# LcsNodes-Extension-Turnout-Servo-and-Rel.net
KiCad netlist of a schematic drawn in EasyEDA
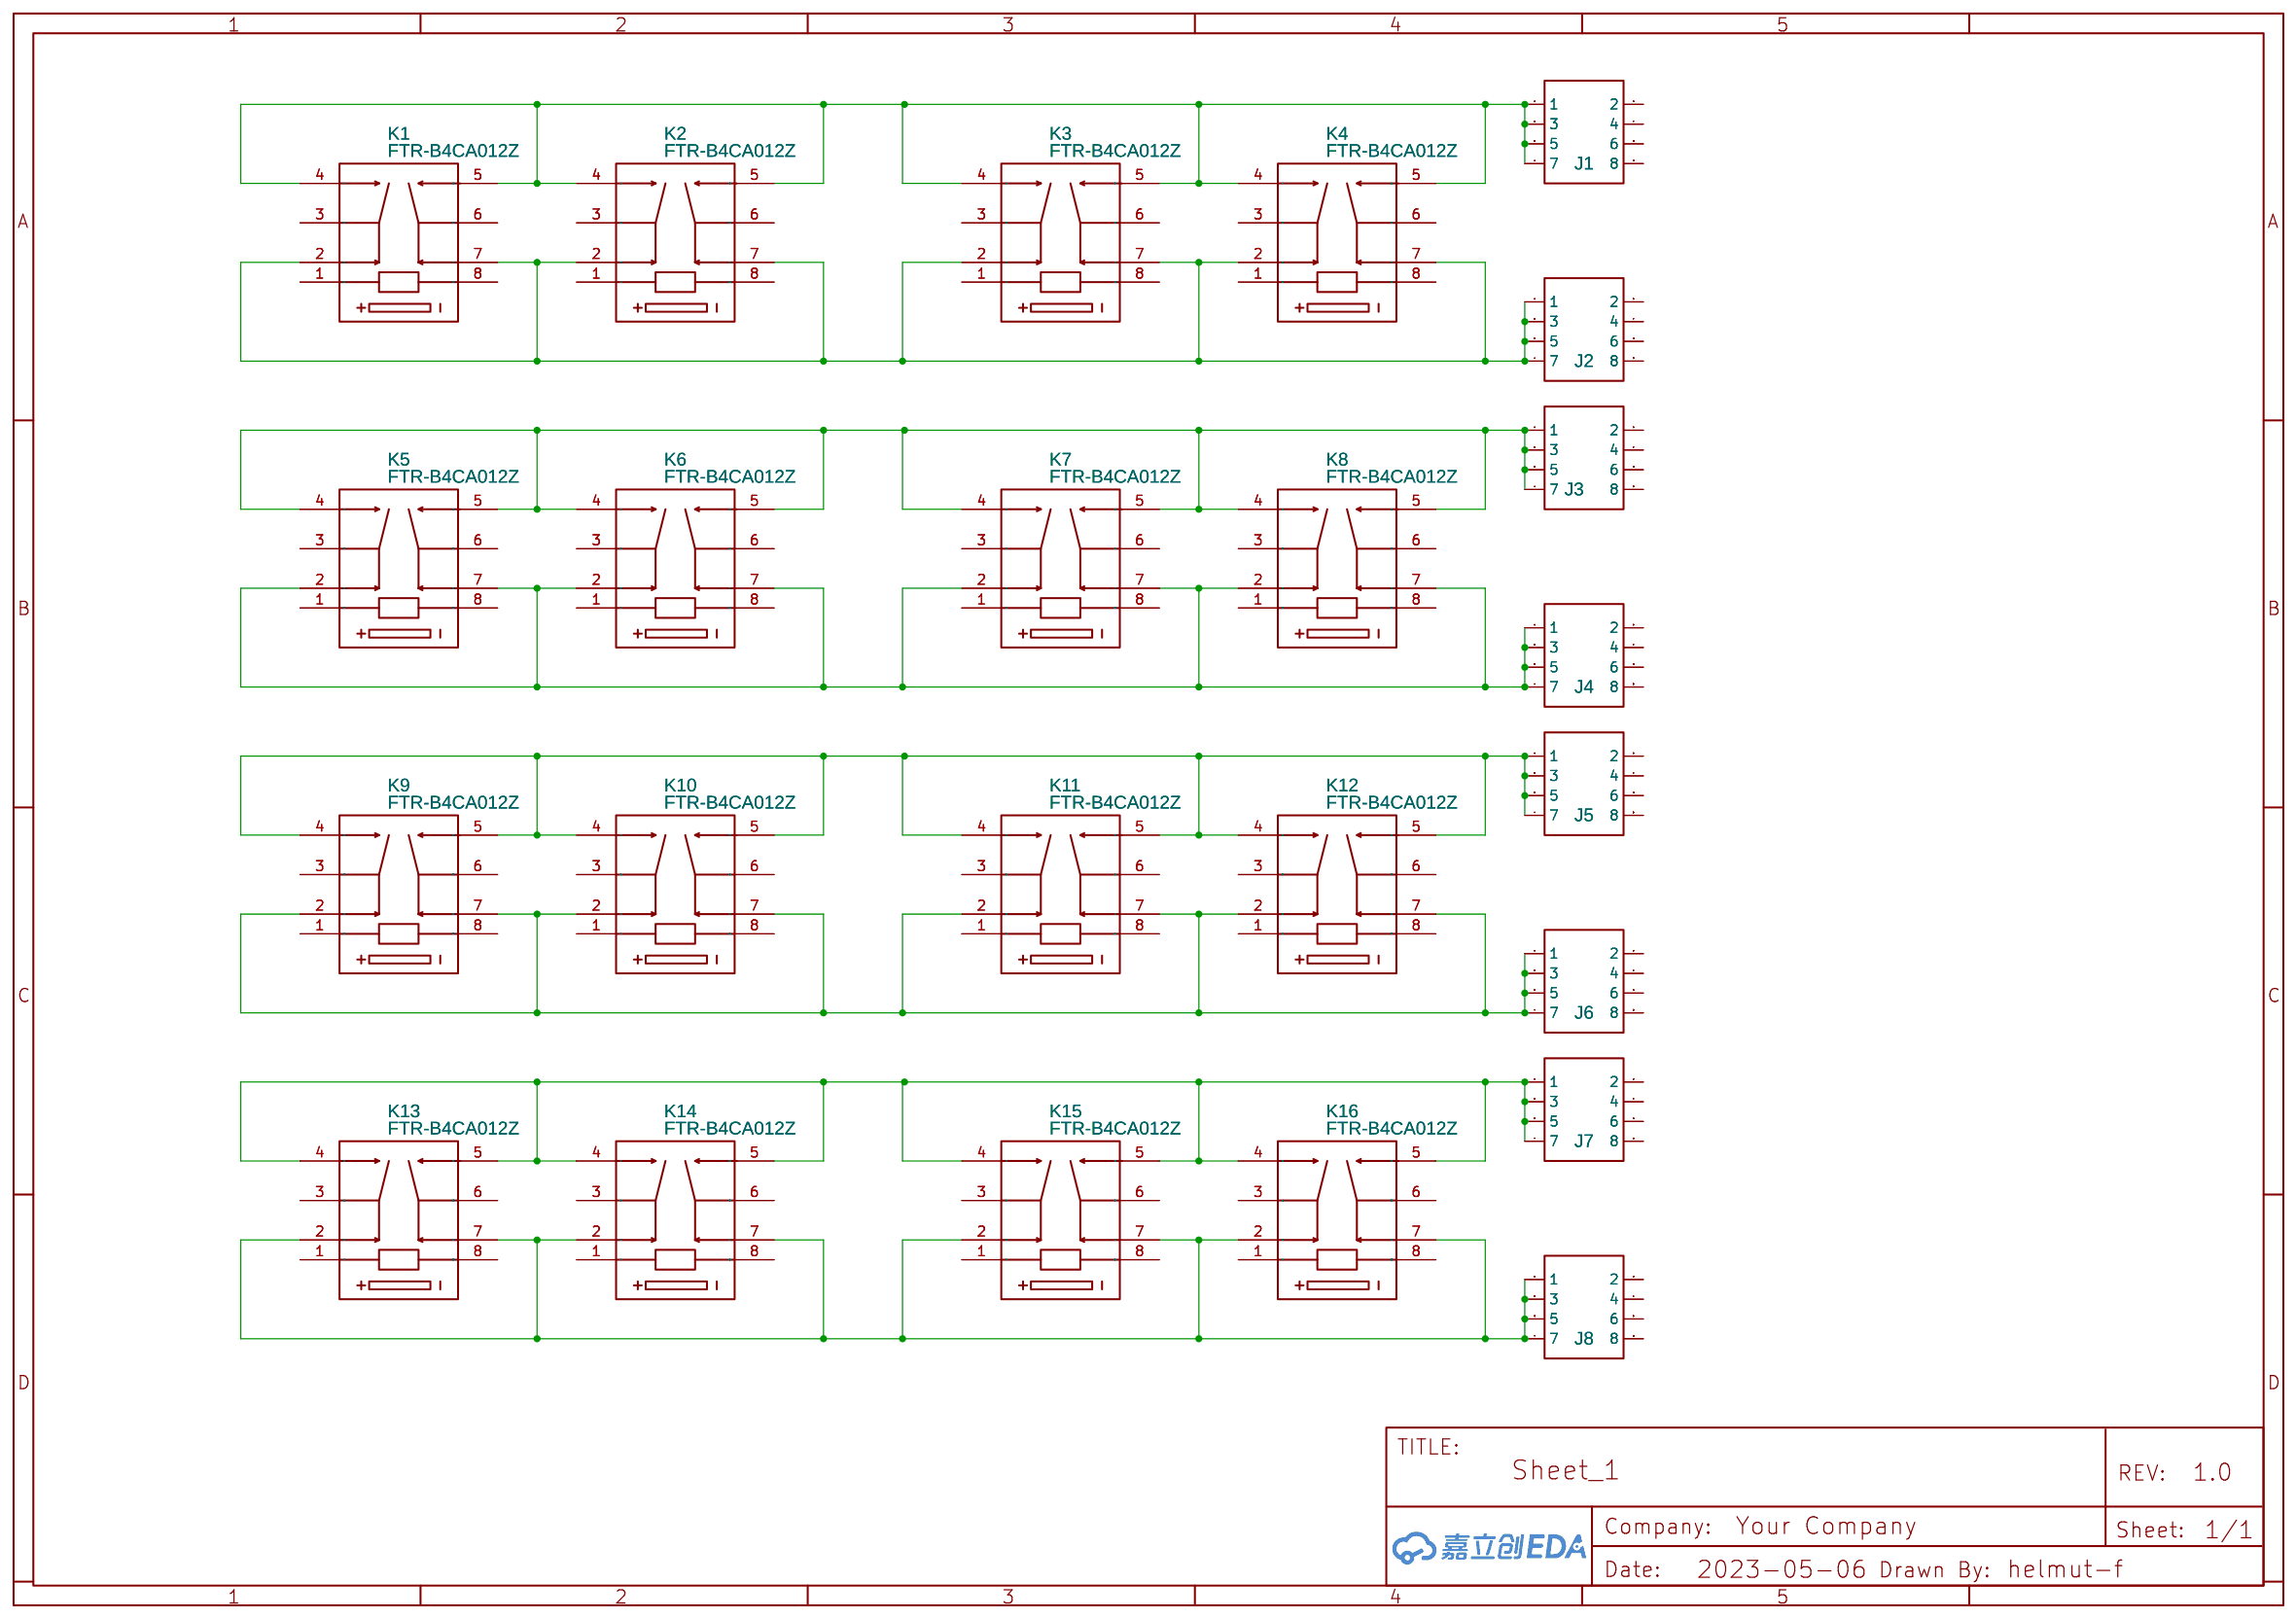
[diagram p0: Sheet_1]
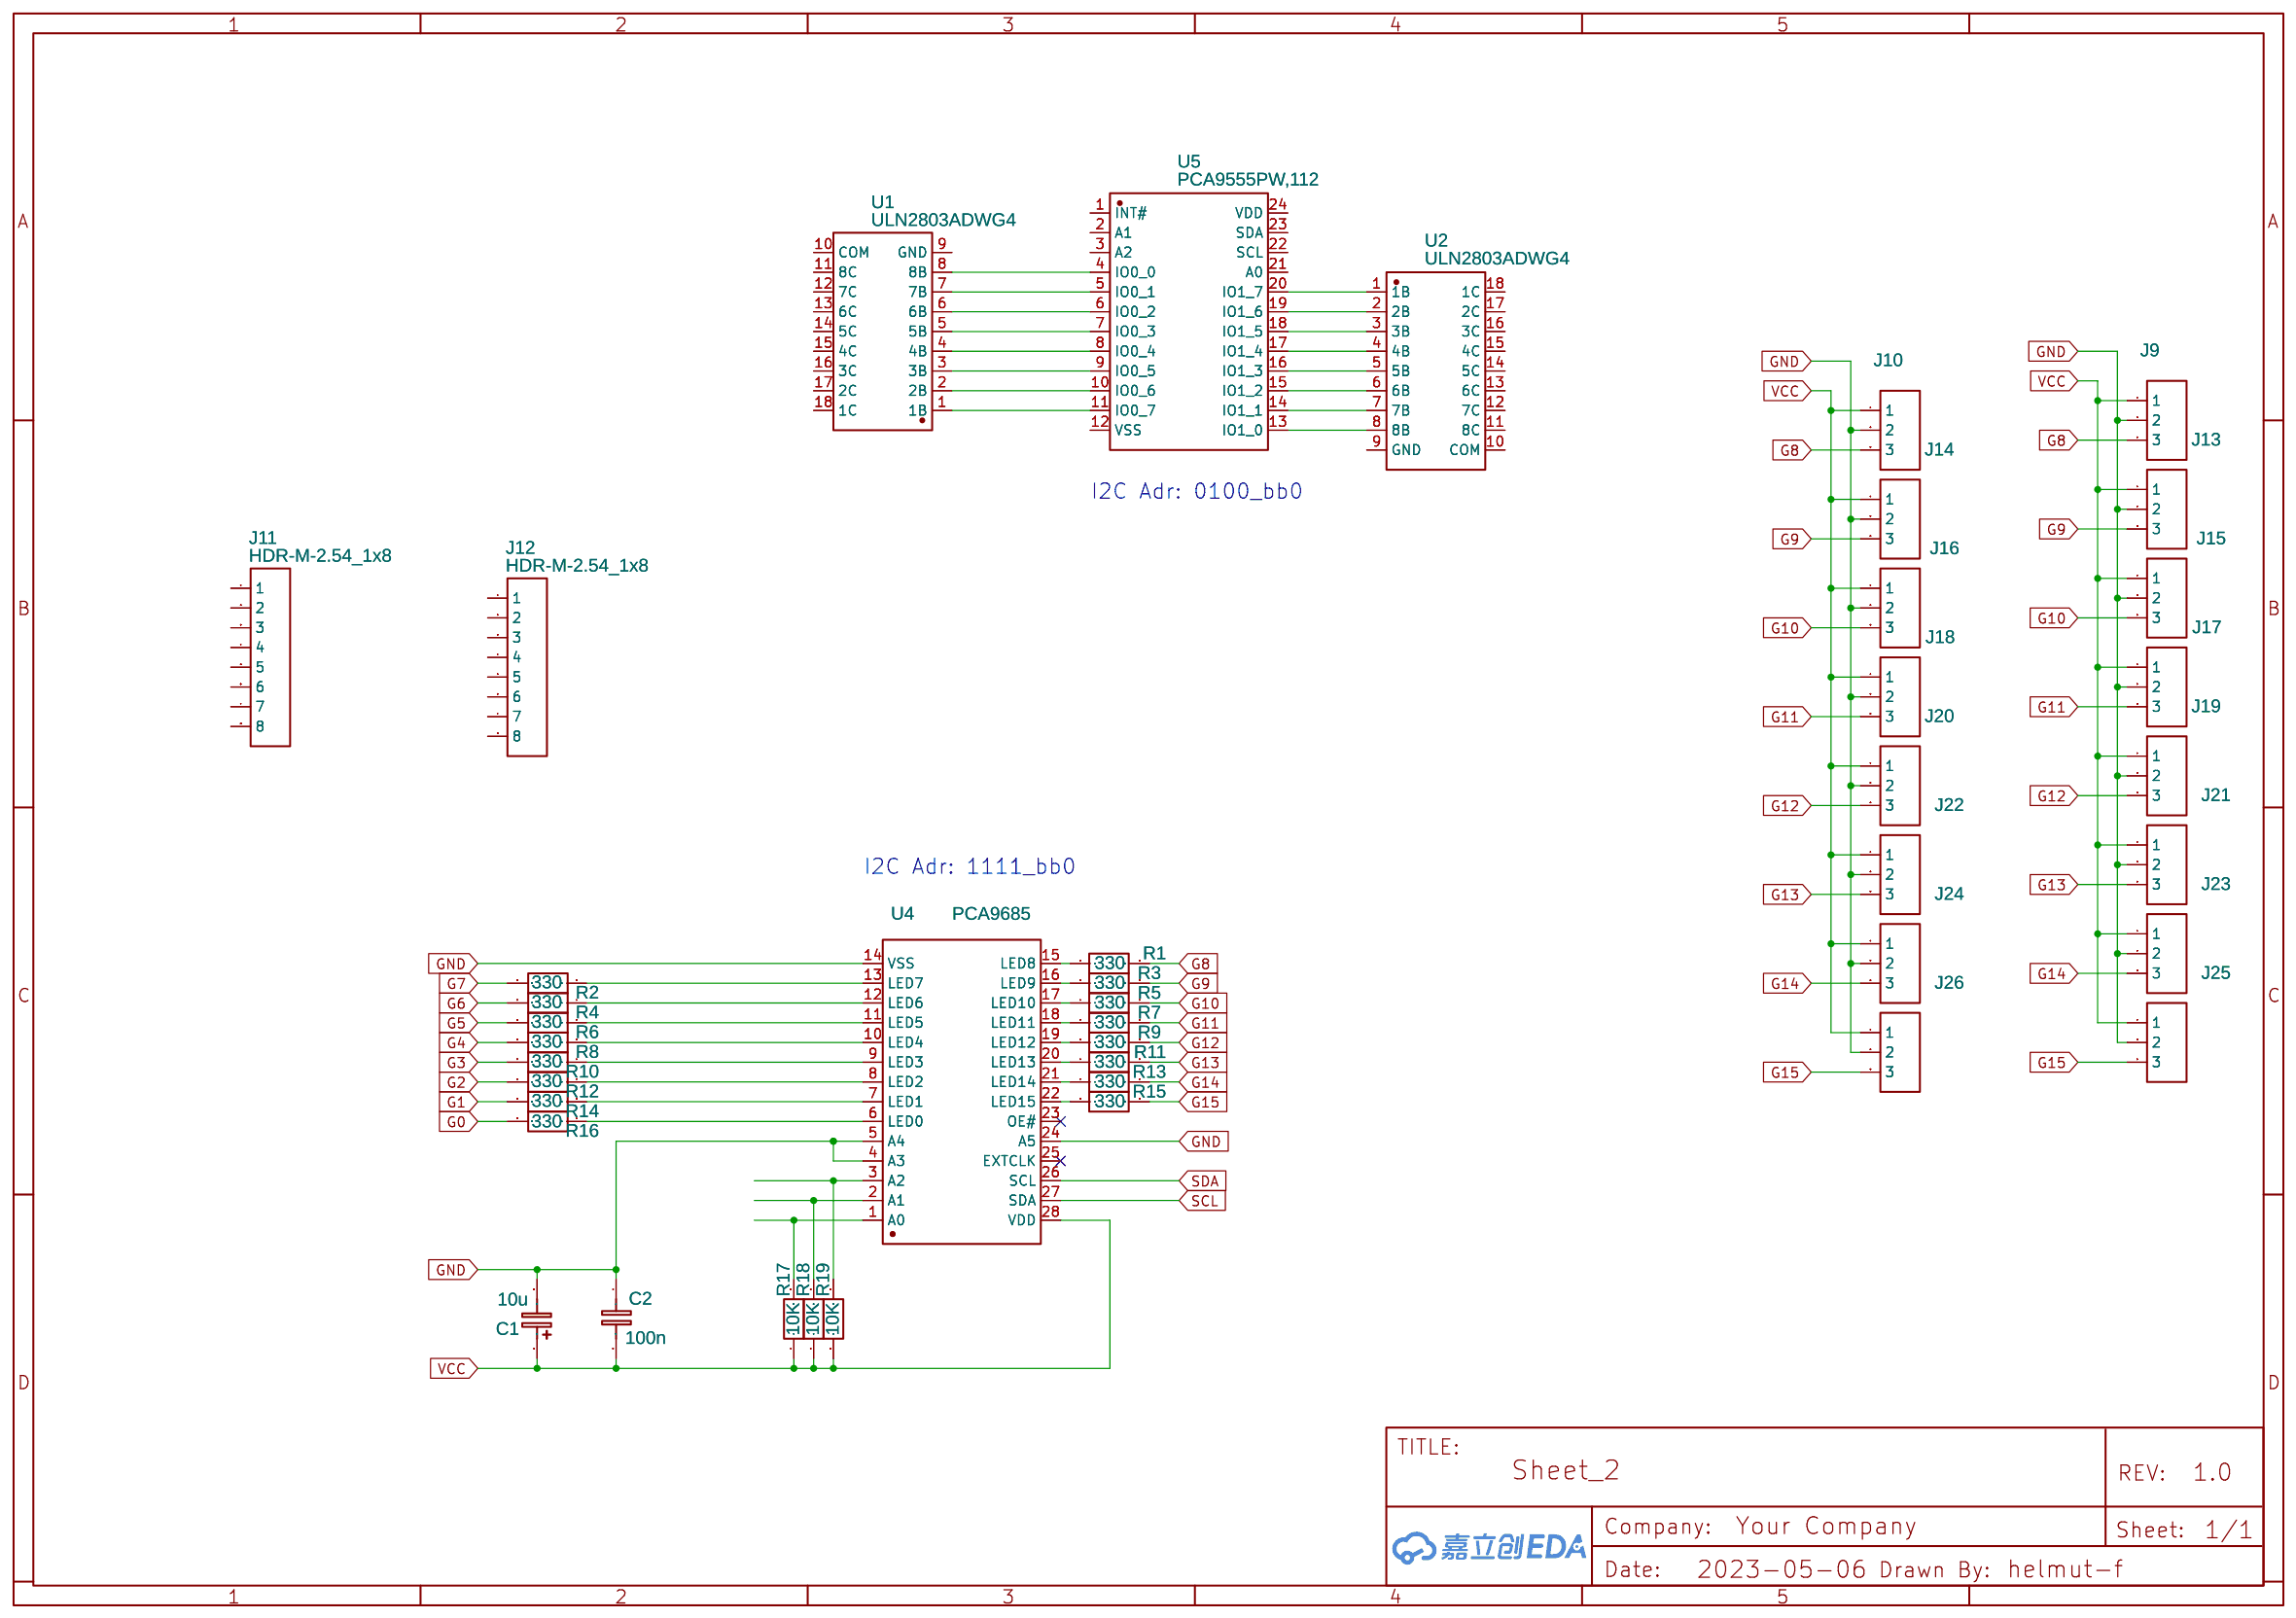
[diagram p1: Sheet_2]
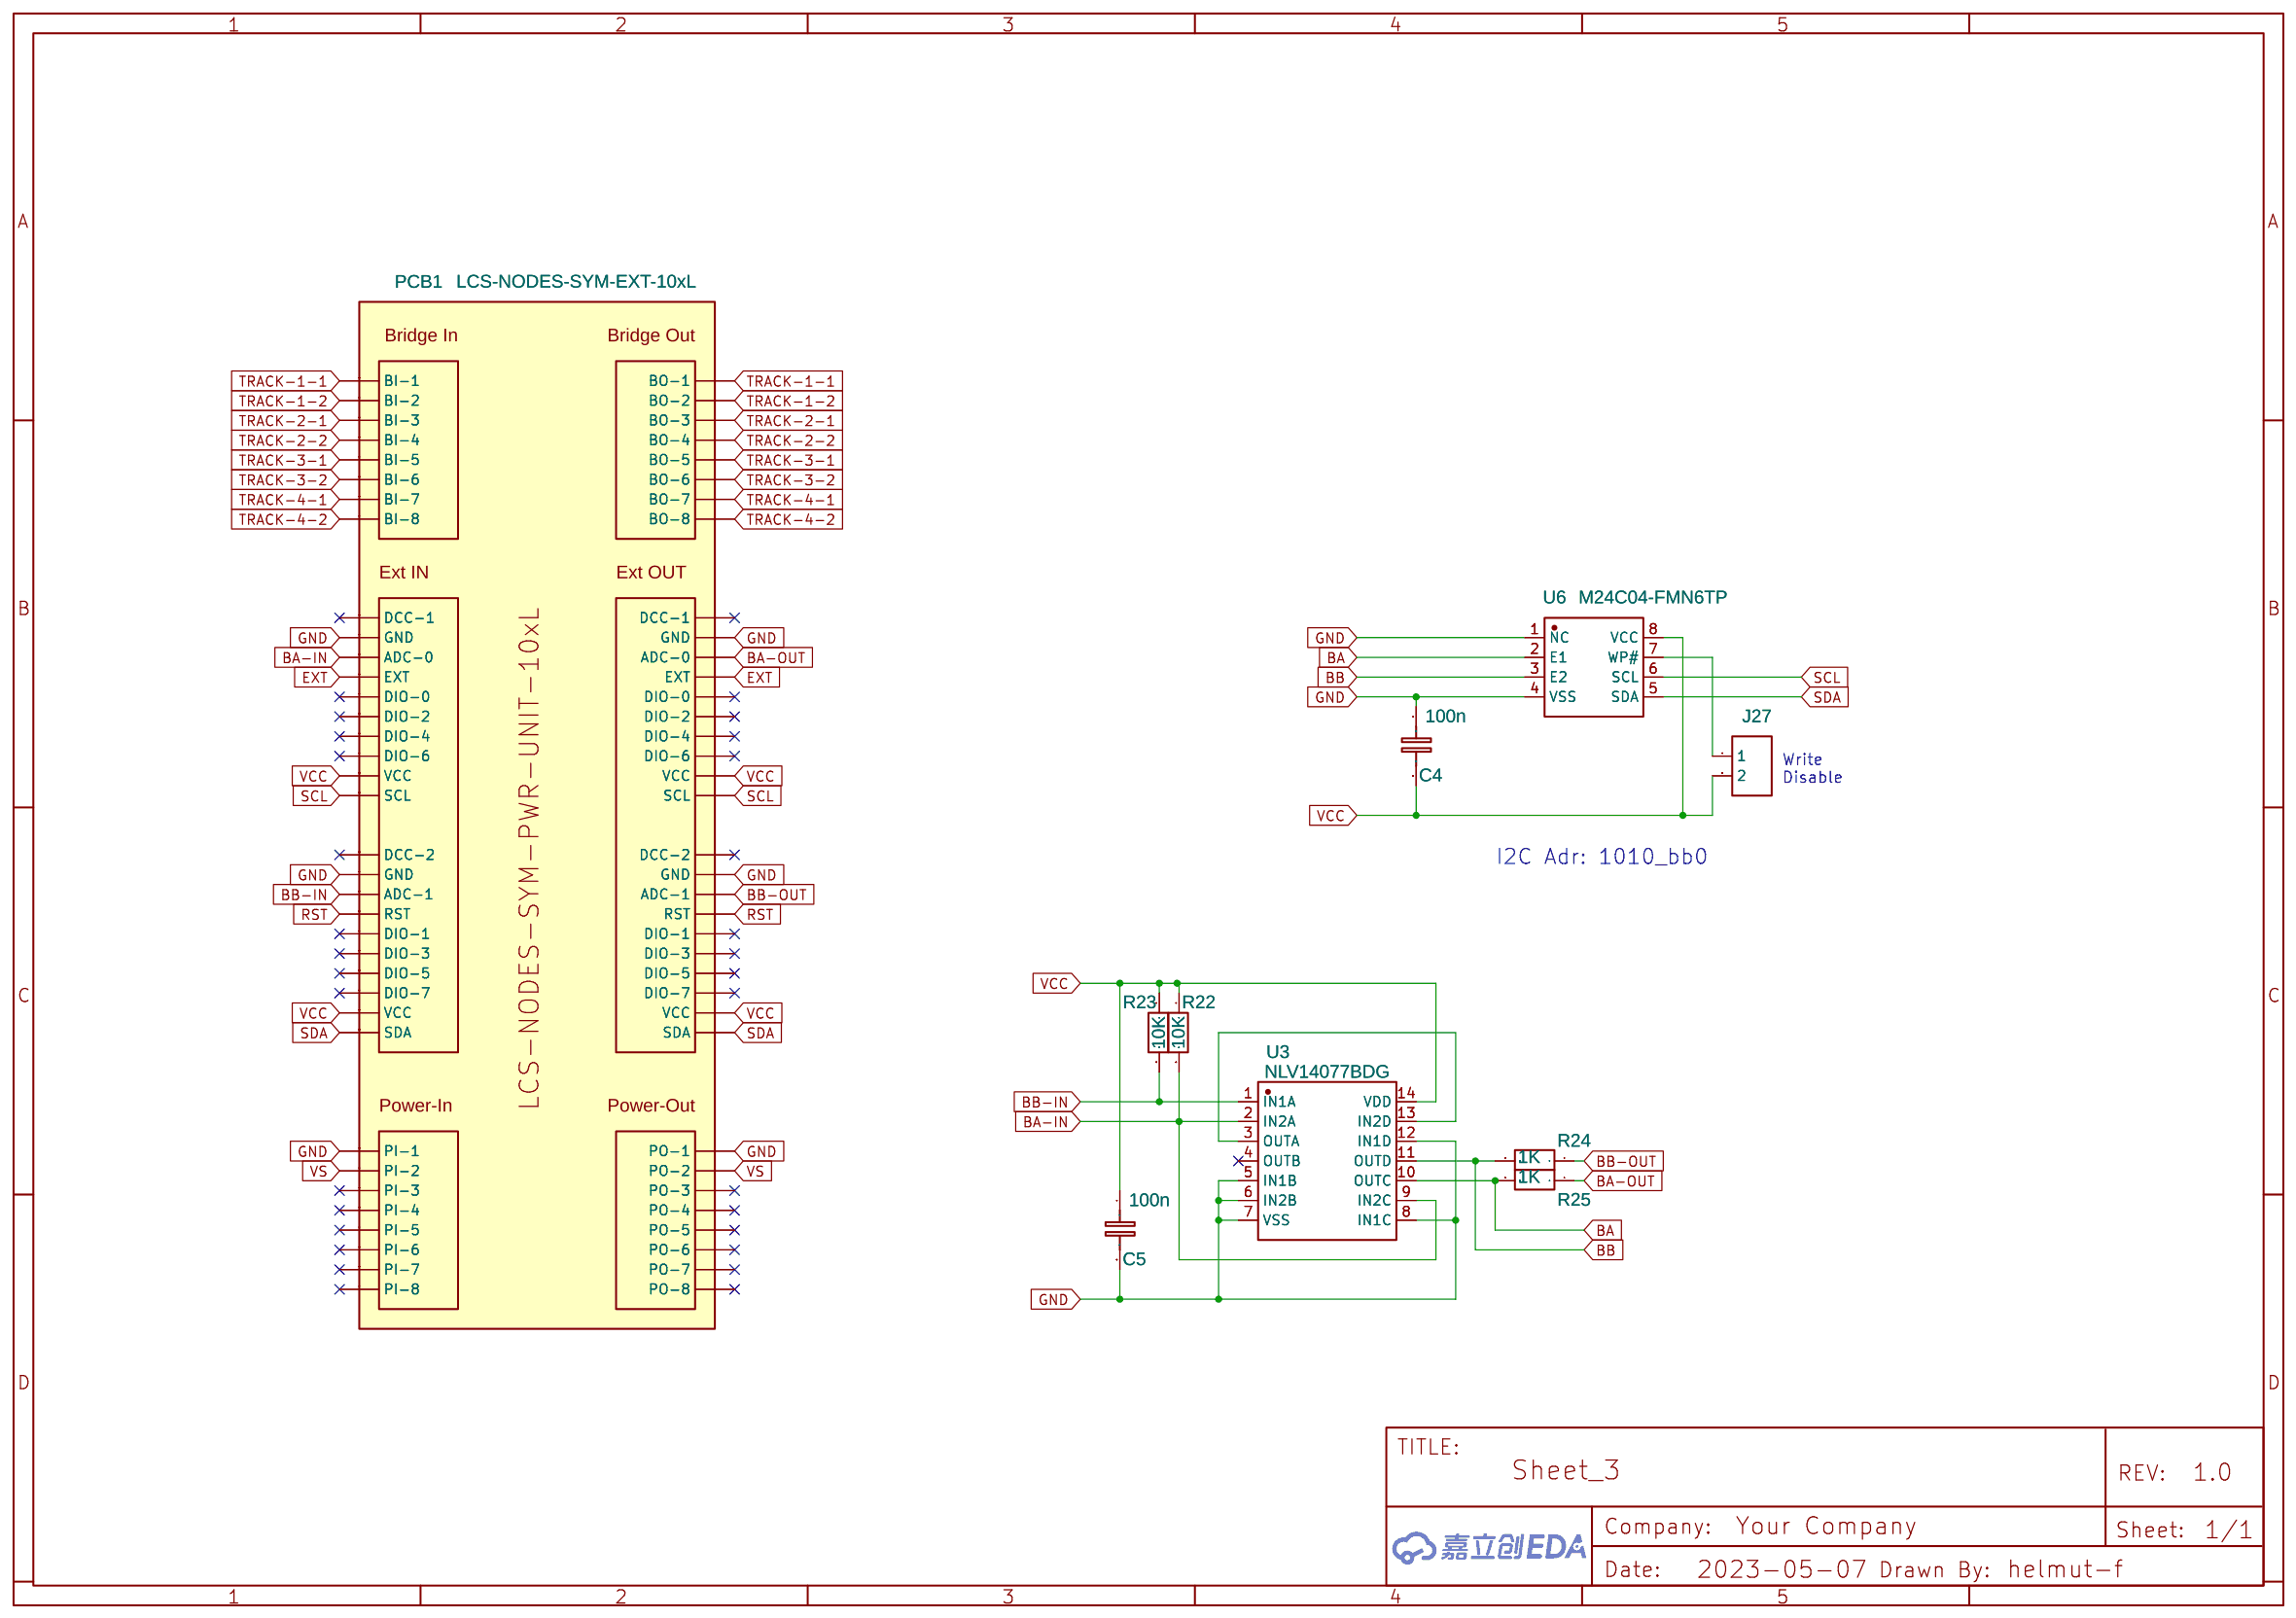
[diagram p2: Sheet_3]

(export (version "E")
  (design (tool "Eeschema 10.0.6"))
  (components
    (comp (ref "J1")
      (value "HDR-M-2.54_2x4")
      (fields (field (name "BOM_Supplier Part") "C58363"))
      (libsource (lib "") (part "HDR-M-2.54_2x4"))
    )
    (comp (ref "J2")
      (value "HDR-M-2.54_2x4")
      (fields (field (name "BOM_Supplier Part") "C58363"))
      (libsource (lib "") (part "HDR-M-2.54_2x4"))
    )
    (comp (ref "J3")
      (value "HDR-M-2.54_2x4")
      (fields (field (name "BOM_Supplier Part") "C58363"))
      (libsource (lib "") (part "HDR-M-2.54_2x4"))
    )
    (comp (ref "J4")
      (value "HDR-M-2.54_2x4")
      (fields (field (name "BOM_Supplier Part") "C58363"))
      (libsource (lib "") (part "HDR-M-2.54_2x4"))
    )
    (comp (ref "J5")
      (value "HDR-M-2.54_2x4")
      (fields (field (name "BOM_Supplier Part") "C58363"))
      (libsource (lib "") (part "HDR-M-2.54_2x4"))
    )
    (comp (ref "J6")
      (value "HDR-M-2.54_2x4")
      (fields (field (name "BOM_Supplier Part") "C58363"))
      (libsource (lib "") (part "HDR-M-2.54_2x4"))
    )
    (comp (ref "J7")
      (value "HDR-M-2.54_2x4")
      (fields (field (name "BOM_Supplier Part") "C58363"))
      (libsource (lib "") (part "HDR-M-2.54_2x4"))
    )
    (comp (ref "J8")
      (value "HDR-M-2.54_2x4")
      (fields (field (name "BOM_Supplier Part") "C58363"))
      (libsource (lib "") (part "HDR-M-2.54_2x4"))
    )
    (comp (ref "K1")
      (value "FTR-B4CA012Z")
      (fields (field (name "BOM_Supplier Part") "C1222347"))
      (libsource (lib "") (part "FTR-B4CA012Z"))
    )
    (comp (ref "K2")
      (value "FTR-B4CA012Z")
      (fields (field (name "BOM_Supplier Part") "C1222347"))
      (libsource (lib "") (part "FTR-B4CA012Z"))
    )
    (comp (ref "K3")
      (value "FTR-B4CA012Z")
      (fields (field (name "BOM_Supplier Part") "C1222347"))
      (libsource (lib "") (part "FTR-B4CA012Z"))
    )
    (comp (ref "K4")
      (value "FTR-B4CA012Z")
      (fields (field (name "BOM_Supplier Part") "C1222347"))
      (libsource (lib "") (part "FTR-B4CA012Z"))
    )
    (comp (ref "K5")
      (value "FTR-B4CA012Z")
      (fields (field (name "BOM_Supplier Part") "C1222347"))
      (libsource (lib "") (part "FTR-B4CA012Z"))
    )
    (comp (ref "K6")
      (value "FTR-B4CA012Z")
      (fields (field (name "BOM_Supplier Part") "C1222347"))
      (libsource (lib "") (part "FTR-B4CA012Z"))
    )
    (comp (ref "K7")
      (value "FTR-B4CA012Z")
      (fields (field (name "BOM_Supplier Part") "C1222347"))
      (libsource (lib "") (part "FTR-B4CA012Z"))
    )
    (comp (ref "K8")
      (value "FTR-B4CA012Z")
      (fields (field (name "BOM_Supplier Part") "C1222347"))
      (libsource (lib "") (part "FTR-B4CA012Z"))
    )
    (comp (ref "K9")
      (value "FTR-B4CA012Z")
      (fields (field (name "BOM_Supplier Part") "C1222347"))
      (libsource (lib "") (part "FTR-B4CA012Z"))
    )
    (comp (ref "K10")
      (value "FTR-B4CA012Z")
      (fields (field (name "BOM_Supplier Part") "C1222347"))
      (libsource (lib "") (part "FTR-B4CA012Z"))
    )
    (comp (ref "K11")
      (value "FTR-B4CA012Z")
      (fields (field (name "BOM_Supplier Part") "C1222347"))
      (libsource (lib "") (part "FTR-B4CA012Z"))
    )
    (comp (ref "K12")
      (value "FTR-B4CA012Z")
      (fields (field (name "BOM_Supplier Part") "C1222347"))
      (libsource (lib "") (part "FTR-B4CA012Z"))
    )
    (comp (ref "K13")
      (value "FTR-B4CA012Z")
      (fields (field (name "BOM_Supplier Part") "C1222347"))
      (libsource (lib "") (part "FTR-B4CA012Z"))
    )
    (comp (ref "K14")
      (value "FTR-B4CA012Z")
      (fields (field (name "BOM_Supplier Part") "C1222347"))
      (libsource (lib "") (part "FTR-B4CA012Z"))
    )
    (comp (ref "K15")
      (value "FTR-B4CA012Z")
      (fields (field (name "BOM_Supplier Part") "C1222347"))
      (libsource (lib "") (part "FTR-B4CA012Z"))
    )
    (comp (ref "K16")
      (value "FTR-B4CA012Z")
      (fields (field (name "BOM_Supplier Part") "C1222347"))
      (libsource (lib "") (part "FTR-B4CA012Z"))
    )
    (comp (ref "C1") (value "10u") (libsource (lib "") (part "CE_TH_D4.0×F1.5_EU")))
    (comp (ref "C2") (value "100n") (libsource (lib "") (part "C_0603_EU")))
    (comp (ref "J9")
      (value "HDR-M-2.54_1x3")
      (fields (field (name "BOM_Supplier Part") "C180248"))
      (libsource (lib "") (part "HDR-M-2.54_1x3"))
    )
    (comp (ref "J10")
      (value "HDR-M-2.54_1x3")
      (fields (field (name "BOM_Supplier Part") "C180248"))
      (libsource (lib "") (part "HDR-M-2.54_1x3"))
    )
    (comp (ref "J11")
      (value "HDR-M-2.54_1x8")
      (fields (field (name "BOM_Supplier Part") "C190820"))
      (libsource (lib "") (part "HDR-M-2.54_1x8"))
    )
    (comp (ref "J12")
      (value "HDR-M-2.54_1x8")
      (fields (field (name "BOM_Supplier Part") "C190820"))
      (libsource (lib "") (part "HDR-M-2.54_1x8"))
    )
    (comp (ref "J13")
      (value "HDR-M-2.54_1x3")
      (fields (field (name "BOM_Supplier Part") "C180248"))
      (libsource (lib "") (part "HDR-M-2.54_1x3"))
    )
    (comp (ref "J14")
      (value "HDR-M-2.54_1x3")
      (fields (field (name "BOM_Supplier Part") "C180248"))
      (libsource (lib "") (part "HDR-M-2.54_1x3"))
    )
    (comp (ref "J15")
      (value "HDR-M-2.54_1x3")
      (fields (field (name "BOM_Supplier Part") "C180248"))
      (libsource (lib "") (part "HDR-M-2.54_1x3"))
    )
    (comp (ref "J16")
      (value "HDR-M-2.54_1x3")
      (fields (field (name "BOM_Supplier Part") "C180248"))
      (libsource (lib "") (part "HDR-M-2.54_1x3"))
    )
    (comp (ref "J17")
      (value "HDR-M-2.54_1x3")
      (fields (field (name "BOM_Supplier Part") "C180248"))
      (libsource (lib "") (part "HDR-M-2.54_1x3"))
    )
    (comp (ref "J18")
      (value "HDR-M-2.54_1x3")
      (fields (field (name "BOM_Supplier Part") "C180248"))
      (libsource (lib "") (part "HDR-M-2.54_1x3"))
    )
    (comp (ref "J19")
      (value "HDR-M-2.54_1x3")
      (fields (field (name "BOM_Supplier Part") "C180248"))
      (libsource (lib "") (part "HDR-M-2.54_1x3"))
    )
    (comp (ref "J20")
      (value "HDR-M-2.54_1x3")
      (fields (field (name "BOM_Supplier Part") "C180248"))
      (libsource (lib "") (part "HDR-M-2.54_1x3"))
    )
    (comp (ref "J21")
      (value "HDR-M-2.54_1x3")
      (fields (field (name "BOM_Supplier Part") "C180248"))
      (libsource (lib "") (part "HDR-M-2.54_1x3"))
    )
    (comp (ref "J22")
      (value "HDR-M-2.54_1x3")
      (fields (field (name "BOM_Supplier Part") "C180248"))
      (libsource (lib "") (part "HDR-M-2.54_1x3"))
    )
    (comp (ref "J23")
      (value "HDR-M-2.54_1x3")
      (fields (field (name "BOM_Supplier Part") "C180248"))
      (libsource (lib "") (part "HDR-M-2.54_1x3"))
    )
    (comp (ref "J24")
      (value "HDR-M-2.54_1x3")
      (fields (field (name "BOM_Supplier Part") "C180248"))
      (libsource (lib "") (part "HDR-M-2.54_1x3"))
    )
    (comp (ref "J25")
      (value "HDR-M-2.54_1x3")
      (fields (field (name "BOM_Supplier Part") "C180248"))
      (libsource (lib "") (part "HDR-M-2.54_1x3"))
    )
    (comp (ref "J26")
      (value "HDR-M-2.54_1x3")
      (fields (field (name "BOM_Supplier Part") "C180248"))
      (libsource (lib "") (part "HDR-M-2.54_1x3"))
    )
    (comp (ref "R1") (value "330") (libsource (lib "") (part "R_AXIAL-0.3_EU_1")))
    (comp (ref "R2") (value "330") (libsource (lib "") (part "R_AXIAL-0.3_EU")))
    (comp (ref "R3") (value "330") (libsource (lib "") (part "R_AXIAL-0.3_EU_1")))
    (comp (ref "R4") (value "330") (libsource (lib "") (part "R_AXIAL-0.3_EU")))
    (comp (ref "R5") (value "330") (libsource (lib "") (part "R_AXIAL-0.3_EU_1")))
    (comp (ref "R6") (value "330") (libsource (lib "") (part "R_AXIAL-0.3_EU")))
    (comp (ref "R7") (value "330") (libsource (lib "") (part "R_AXIAL-0.3_EU_1")))
    (comp (ref "R8") (value "330") (libsource (lib "") (part "R_AXIAL-0.3_EU")))
    (comp (ref "R9") (value "330") (libsource (lib "") (part "R_AXIAL-0.3_EU_1")))
    (comp (ref "R10") (value "330") (libsource (lib "") (part "R_AXIAL-0.3_EU")))
    (comp (ref "R11") (value "330") (libsource (lib "") (part "R_AXIAL-0.3_EU_1")))
    (comp (ref "R12") (value "330") (libsource (lib "") (part "R_AXIAL-0.3_EU")))
    (comp (ref "R13") (value "330") (libsource (lib "") (part "R_AXIAL-0.3_EU_1")))
    (comp (ref "R14") (value "330") (libsource (lib "") (part "R_AXIAL-0.3_EU")))
    (comp (ref "R15") (value "330") (libsource (lib "") (part "R_AXIAL-0.3_EU_1")))
    (comp (ref "R16") (value "330") (libsource (lib "") (part "R_AXIAL-0.3_EU")))
    (comp (ref "R17") (value "10K") (libsource (lib "") (part "R_1206_EU")))
    (comp (ref "R18") (value "10K") (libsource (lib "") (part "R_1206_EU")))
    (comp (ref "R19") (value "10K") (libsource (lib "") (part "R_1206_EU")))
    (comp (ref "U1")
      (value "ULN2803ADWG4")
      (fields (field (name "BOM_Supplier Part") "C4365973"))
      (libsource (lib "") (part "ULN2803ADWG4_1"))
    )
    (comp (ref "U2")
      (value "ULN2803ADWG4")
      (fields (field (name "BOM_Supplier Part") "C4365973"))
      (libsource (lib "") (part "ULN2803ADWG4"))
    )
    (comp (ref "U4")
      (value "PCA9685")
      (fields
        (field (name "BOM_Manufacturer Part") "PCA9685PW/Q900,118")
        (field (name "BOM_Supplier Part") "C92206")
      )
      (libsource (lib "") (part "PCA9685PW/Q900,118"))
    )
    (comp (ref "U5")
      (value "PCA9555PW,112")
      (fields (field (name "BOM_Supplier Part") "C2688893"))
      (libsource (lib "") (part "PCA9555PW,112"))
    )
    (comp (ref "C4") (value "100n") (libsource (lib "") (part "C_0603_EU")))
    (comp (ref "C5") (value "100n") (libsource (lib "") (part "C_0603_EU")))
    (comp (ref "J27") (value "HDR-M-2.54_1x2") (libsource (lib "") (part "HDR-M-2.54_1x2")))
    (comp (ref "PCB1") (value "LCS-NODES-SYM-EXT-10xL") (libsource (lib "") (part "LCS-NODES-SYM-EXT-10xL")))
    (comp (ref "R22") (value "10K") (libsource (lib "") (part "R_AXIAL-0.3_EU")))
    (comp (ref "R23") (value "10K") (libsource (lib "") (part "R_AXIAL-0.3_EU")))
    (comp (ref "R24") (value "1K") (libsource (lib "") (part "R_AXIAL-0.3_EU_1")))
    (comp (ref "R25") (value "1K") (libsource (lib "") (part "R_AXIAL-0.3_EU_1")))
    (comp (ref "U3")
      (value "NLV14077BDG")
      (fields (field (name "Manufacturer") "onsemi(安森美)"))
      (libsource (lib "") (part "NLV14077BDG"))
    )
    (comp (ref "U6")
      (value "M24C04-FMN6TP")
      (fields (field (name "Manufacturer") "ST(意法半导体)"))
      (libsource (lib "") (part "M24C04-FMN6TP"))
    )
  )
  (nets
    (net (code "1") (name "BA") (class "Default")
      (node (ref "R25") (pin "2") (pinfunction "2_2") (pintype "unspecified"))
      (node (ref "U3") (pin "10") (pinfunction "OUTC_10") (pintype "unspecified"))
      (node (ref "U6") (pin "2") (pinfunction "E1_2") (pintype "unspecified"))
    )
    (net (code "2") (name "BA-IN") (class "Default")
      (node (ref "PCB1") (pin "22") (pinfunction "ADC-0_22") (pintype "unspecified"))
      (node (ref "R22") (pin "2") (pinfunction "2_2") (pintype "unspecified"))
      (node (ref "U3") (pin "2") (pinfunction "IN2A_2") (pintype "unspecified"))
      (node (ref "U3") (pin "9") (pinfunction "IN2C_9") (pintype "unspecified"))
    )
    (net (code "3") (name "BA-OUT") (class "Default")
      (node (ref "PCB1") (pin "62") (pinfunction "ADC-0_62") (pintype "unspecified"))
      (node (ref "R25") (pin "1") (pinfunction "1_1") (pintype "unspecified"))
    )
    (net (code "4") (name "BB") (class "Default")
      (node (ref "R24") (pin "2") (pinfunction "2_2") (pintype "unspecified"))
      (node (ref "U3") (pin "11") (pinfunction "OUTD_11") (pintype "unspecified"))
      (node (ref "U6") (pin "3") (pinfunction "E2_3") (pintype "unspecified"))
    )
    (net (code "5") (name "BB-IN") (class "Default")
      (node (ref "PCB1") (pin "32") (pinfunction "ADC-1_32") (pintype "unspecified"))
      (node (ref "R23") (pin "2") (pinfunction "2_2") (pintype "unspecified"))
      (node (ref "U3") (pin "1") (pinfunction "IN1A_1") (pintype "unspecified"))
    )
    (net (code "6") (name "BB-OUT") (class "Default")
      (node (ref "PCB1") (pin "72") (pinfunction "ADC-1_72") (pintype "unspecified"))
      (node (ref "R24") (pin "1") (pinfunction "1_1") (pintype "unspecified"))
    )
    (net (code "7") (name "EXT") (class "Default")
      (node (ref "PCB1") (pin "23") (pinfunction "EXT_23") (pintype "unspecified"))
      (node (ref "PCB1") (pin "63") (pinfunction "EXT_63") (pintype "unspecified"))
    )
    (net (code "8") (name "G0") (class "Default")
      (node (ref "R16") (pin "2") (pinfunction "2_2") (pintype "unspecified"))
    )
    (net (code "9") (name "G1") (class "Default")
      (node (ref "R14") (pin "2") (pinfunction "2_2") (pintype "unspecified"))
    )
    (net (code "10") (name "G2") (class "Default")
      (node (ref "R12") (pin "2") (pinfunction "2_2") (pintype "unspecified"))
    )
    (net (code "11") (name "G3") (class "Default")
      (node (ref "R10") (pin "2") (pinfunction "2_2") (pintype "unspecified"))
    )
    (net (code "12") (name "G4") (class "Default")
      (node (ref "R8") (pin "2") (pinfunction "2_2") (pintype "unspecified"))
    )
    (net (code "13") (name "G5") (class "Default")
      (node (ref "R6") (pin "2") (pinfunction "2_2") (pintype "unspecified"))
    )
    (net (code "14") (name "G6") (class "Default")
      (node (ref "R4") (pin "2") (pinfunction "2_2") (pintype "unspecified"))
    )
    (net (code "15") (name "G7") (class "Default")
      (node (ref "R2") (pin "2") (pinfunction "2_2") (pintype "unspecified"))
    )
    (net (code "16") (name "G8") (class "Default")
      (node (ref "J10") (pin "3") (pinfunction "3_3") (pintype "input"))
      (node (ref "J9") (pin "3") (pinfunction "3_3") (pintype "input"))
      (node (ref "R1") (pin "2") (pinfunction "2_2") (pintype "unspecified"))
    )
    (net (code "17") (name "G9") (class "Default")
      (node (ref "J13") (pin "3") (pinfunction "3_3") (pintype "input"))
      (node (ref "J14") (pin "3") (pinfunction "3_3") (pintype "input"))
      (node (ref "R3") (pin "2") (pinfunction "2_2") (pintype "unspecified"))
    )
    (net (code "18") (name "G10") (class "Default")
      (node (ref "J15") (pin "3") (pinfunction "3_3") (pintype "input"))
      (node (ref "J16") (pin "3") (pinfunction "3_3") (pintype "input"))
      (node (ref "R5") (pin "2") (pinfunction "2_2") (pintype "unspecified"))
    )
    (net (code "19") (name "G11") (class "Default")
      (node (ref "J17") (pin "3") (pinfunction "3_3") (pintype "input"))
      (node (ref "J18") (pin "3") (pinfunction "3_3") (pintype "input"))
      (node (ref "R7") (pin "2") (pinfunction "2_2") (pintype "unspecified"))
    )
    (net (code "20") (name "G12") (class "Default")
      (node (ref "J19") (pin "3") (pinfunction "3_3") (pintype "input"))
      (node (ref "J20") (pin "3") (pinfunction "3_3") (pintype "input"))
      (node (ref "R9") (pin "2") (pinfunction "2_2") (pintype "unspecified"))
    )
    (net (code "21") (name "G13") (class "Default")
      (node (ref "J21") (pin "3") (pinfunction "3_3") (pintype "input"))
      (node (ref "J22") (pin "3") (pinfunction "3_3") (pintype "input"))
      (node (ref "R11") (pin "2") (pinfunction "2_2") (pintype "unspecified"))
    )
    (net (code "22") (name "G14") (class "Default")
      (node (ref "J23") (pin "3") (pinfunction "3_3") (pintype "input"))
      (node (ref "J24") (pin "3") (pinfunction "3_3") (pintype "input"))
      (node (ref "R13") (pin "2") (pinfunction "2_2") (pintype "unspecified"))
    )
    (net (code "23") (name "G15") (class "Default")
      (node (ref "J25") (pin "3") (pinfunction "3_3") (pintype "input"))
      (node (ref "J26") (pin "3") (pinfunction "3_3") (pintype "input"))
      (node (ref "R15") (pin "2") (pinfunction "2_2") (pintype "unspecified"))
    )
    (net (code "24") (name "GND") (class "Default")
      (node (ref "C1") (pin "2") (pinfunction "2_2") (pintype "unspecified"))
      (node (ref "C2") (pin "1") (pinfunction "1_1") (pintype "unspecified"))
      (node (ref "C4") (pin "1") (pinfunction "1_1") (pintype "unspecified"))
      (node (ref "C5") (pin "2") (pinfunction "2_2") (pintype "unspecified"))
      (node (ref "J10") (pin "2") (pinfunction "2_2") (pintype "input"))
      (node (ref "J13") (pin "2") (pinfunction "2_2") (pintype "input"))
      (node (ref "J14") (pin "2") (pinfunction "2_2") (pintype "input"))
      (node (ref "J15") (pin "2") (pinfunction "2_2") (pintype "input"))
      (node (ref "J16") (pin "2") (pinfunction "2_2") (pintype "input"))
      (node (ref "J17") (pin "2") (pinfunction "2_2") (pintype "input"))
      (node (ref "J18") (pin "2") (pinfunction "2_2") (pintype "input"))
      (node (ref "J19") (pin "2") (pinfunction "2_2") (pintype "input"))
      (node (ref "J20") (pin "2") (pinfunction "2_2") (pintype "input"))
      (node (ref "J21") (pin "2") (pinfunction "2_2") (pintype "input"))
      (node (ref "J22") (pin "2") (pinfunction "2_2") (pintype "input"))
      (node (ref "J23") (pin "2") (pinfunction "2_2") (pintype "input"))
      (node (ref "J24") (pin "2") (pinfunction "2_2") (pintype "input"))
      (node (ref "J25") (pin "2") (pinfunction "2_2") (pintype "input"))
      (node (ref "J26") (pin "2") (pinfunction "2_2") (pintype "input"))
      (node (ref "J9") (pin "2") (pinfunction "2_2") (pintype "input"))
      (node (ref "PCB1") (pin "21") (pinfunction "GND_21") (pintype "unspecified"))
      (node (ref "PCB1") (pin "31") (pinfunction "GND_31") (pintype "unspecified"))
      (node (ref "PCB1") (pin "40") (pinfunction "PI-1_40") (pintype "unspecified"))
      (node (ref "PCB1") (pin "61") (pinfunction "GND_61") (pintype "unspecified"))
      (node (ref "PCB1") (pin "71") (pinfunction "GND_71") (pintype "unspecified"))
      (node (ref "PCB1") (pin "80") (pinfunction "PO-1_80") (pintype "unspecified"))
      (node (ref "U3") (pin "12") (pinfunction "IN1D_12") (pintype "unspecified"))
      (node (ref "U3") (pin "5") (pinfunction "IN1B_5") (pintype "unspecified"))
      (node (ref "U3") (pin "6") (pinfunction "IN2B_6") (pintype "unspecified"))
      (node (ref "U3") (pin "7") (pinfunction "VSS_7") (pintype "unspecified"))
      (node (ref "U3") (pin "8") (pinfunction "IN1C_8") (pintype "unspecified"))
      (node (ref "U4") (pin "14") (pinfunction "VSS_14") (pintype "unspecified"))
      (node (ref "U4") (pin "24") (pinfunction "A5_24") (pintype "unspecified"))
      (node (ref "U4") (pin "4") (pinfunction "A3_4") (pintype "unspecified"))
      (node (ref "U4") (pin "5") (pinfunction "A4_5") (pintype "unspecified"))
      (node (ref "U6") (pin "1") (pinfunction "NC_1") (pintype "unspecified"))
      (node (ref "U6") (pin "4") (pinfunction "VSS_4") (pintype "unspecified"))
    )
    (net (code "25") (name "Net-(J1-Pad1)") (class "Default")
      (node (ref "J1") (pin "1") (pinfunction "1_1") (pintype "unspecified"))
      (node (ref "J1") (pin "3") (pinfunction "3_3") (pintype "unspecified"))
      (node (ref "J1") (pin "5") (pinfunction "5_5") (pintype "unspecified"))
      (node (ref "J1") (pin "7") (pinfunction "7_7") (pintype "unspecified"))
      (node (ref "K1") (pin "4") (pinfunction "4_4") (pintype "unspecified"))
      (node (ref "K1") (pin "5") (pinfunction "5_5") (pintype "unspecified"))
      (node (ref "K2") (pin "4") (pinfunction "4_4") (pintype "unspecified"))
      (node (ref "K2") (pin "5") (pinfunction "5_5") (pintype "unspecified"))
      (node (ref "K3") (pin "4") (pinfunction "4_4") (pintype "unspecified"))
      (node (ref "K3") (pin "5") (pinfunction "5_5") (pintype "unspecified"))
      (node (ref "K4") (pin "4") (pinfunction "4_4") (pintype "unspecified"))
      (node (ref "K4") (pin "5") (pinfunction "5_5") (pintype "unspecified"))
    )
    (net (code "26") (name "Net-(J2-Pad1)") (class "Default")
      (node (ref "J2") (pin "1") (pinfunction "1_1") (pintype "unspecified"))
      (node (ref "J2") (pin "3") (pinfunction "3_3") (pintype "unspecified"))
      (node (ref "J2") (pin "5") (pinfunction "5_5") (pintype "unspecified"))
      (node (ref "J2") (pin "7") (pinfunction "7_7") (pintype "unspecified"))
      (node (ref "K1") (pin "2") (pinfunction "2_2") (pintype "unspecified"))
      (node (ref "K1") (pin "7") (pinfunction "7_7") (pintype "unspecified"))
      (node (ref "K2") (pin "2") (pinfunction "2_2") (pintype "unspecified"))
      (node (ref "K2") (pin "7") (pinfunction "7_7") (pintype "unspecified"))
      (node (ref "K3") (pin "2") (pinfunction "2_2") (pintype "unspecified"))
      (node (ref "K3") (pin "7") (pinfunction "7_7") (pintype "unspecified"))
      (node (ref "K4") (pin "2") (pinfunction "2_2") (pintype "unspecified"))
      (node (ref "K4") (pin "7") (pinfunction "7_7") (pintype "unspecified"))
    )
    (net (code "27") (name "Net-(J3-Pad1)") (class "Default")
      (node (ref "J3") (pin "1") (pinfunction "1_1") (pintype "unspecified"))
      (node (ref "J3") (pin "3") (pinfunction "3_3") (pintype "unspecified"))
      (node (ref "J3") (pin "5") (pinfunction "5_5") (pintype "unspecified"))
      (node (ref "J3") (pin "7") (pinfunction "7_7") (pintype "unspecified"))
      (node (ref "K5") (pin "4") (pinfunction "4_4") (pintype "unspecified"))
      (node (ref "K5") (pin "5") (pinfunction "5_5") (pintype "unspecified"))
      (node (ref "K6") (pin "4") (pinfunction "4_4") (pintype "unspecified"))
      (node (ref "K6") (pin "5") (pinfunction "5_5") (pintype "unspecified"))
      (node (ref "K7") (pin "4") (pinfunction "4_4") (pintype "unspecified"))
      (node (ref "K7") (pin "5") (pinfunction "5_5") (pintype "unspecified"))
      (node (ref "K8") (pin "4") (pinfunction "4_4") (pintype "unspecified"))
      (node (ref "K8") (pin "5") (pinfunction "5_5") (pintype "unspecified"))
    )
    (net (code "28") (name "Net-(J4-Pad1)") (class "Default")
      (node (ref "J4") (pin "1") (pinfunction "1_1") (pintype "unspecified"))
      (node (ref "J4") (pin "3") (pinfunction "3_3") (pintype "unspecified"))
      (node (ref "J4") (pin "5") (pinfunction "5_5") (pintype "unspecified"))
      (node (ref "J4") (pin "7") (pinfunction "7_7") (pintype "unspecified"))
      (node (ref "K5") (pin "2") (pinfunction "2_2") (pintype "unspecified"))
      (node (ref "K5") (pin "7") (pinfunction "7_7") (pintype "unspecified"))
      (node (ref "K6") (pin "2") (pinfunction "2_2") (pintype "unspecified"))
      (node (ref "K6") (pin "7") (pinfunction "7_7") (pintype "unspecified"))
      (node (ref "K7") (pin "2") (pinfunction "2_2") (pintype "unspecified"))
      (node (ref "K7") (pin "7") (pinfunction "7_7") (pintype "unspecified"))
      (node (ref "K8") (pin "2") (pinfunction "2_2") (pintype "unspecified"))
      (node (ref "K8") (pin "7") (pinfunction "7_7") (pintype "unspecified"))
    )
    (net (code "29") (name "Net-(J5-Pad1)") (class "Default")
      (node (ref "J5") (pin "1") (pinfunction "1_1") (pintype "unspecified"))
      (node (ref "J5") (pin "3") (pinfunction "3_3") (pintype "unspecified"))
      (node (ref "J5") (pin "5") (pinfunction "5_5") (pintype "unspecified"))
      (node (ref "J5") (pin "7") (pinfunction "7_7") (pintype "unspecified"))
      (node (ref "K10") (pin "4") (pinfunction "4_4") (pintype "unspecified"))
      (node (ref "K10") (pin "5") (pinfunction "5_5") (pintype "unspecified"))
      (node (ref "K11") (pin "4") (pinfunction "4_4") (pintype "unspecified"))
      (node (ref "K11") (pin "5") (pinfunction "5_5") (pintype "unspecified"))
      (node (ref "K12") (pin "4") (pinfunction "4_4") (pintype "unspecified"))
      (node (ref "K12") (pin "5") (pinfunction "5_5") (pintype "unspecified"))
      (node (ref "K9") (pin "4") (pinfunction "4_4") (pintype "unspecified"))
      (node (ref "K9") (pin "5") (pinfunction "5_5") (pintype "unspecified"))
    )
    (net (code "30") (name "Net-(J6-Pad1)") (class "Default")
      (node (ref "J6") (pin "1") (pinfunction "1_1") (pintype "unspecified"))
      (node (ref "J6") (pin "3") (pinfunction "3_3") (pintype "unspecified"))
      (node (ref "J6") (pin "5") (pinfunction "5_5") (pintype "unspecified"))
      (node (ref "J6") (pin "7") (pinfunction "7_7") (pintype "unspecified"))
      (node (ref "K10") (pin "2") (pinfunction "2_2") (pintype "unspecified"))
      (node (ref "K10") (pin "7") (pinfunction "7_7") (pintype "unspecified"))
      (node (ref "K11") (pin "2") (pinfunction "2_2") (pintype "unspecified"))
      (node (ref "K11") (pin "7") (pinfunction "7_7") (pintype "unspecified"))
      (node (ref "K12") (pin "2") (pinfunction "2_2") (pintype "unspecified"))
      (node (ref "K12") (pin "7") (pinfunction "7_7") (pintype "unspecified"))
      (node (ref "K9") (pin "2") (pinfunction "2_2") (pintype "unspecified"))
      (node (ref "K9") (pin "7") (pinfunction "7_7") (pintype "unspecified"))
    )
    (net (code "31") (name "Net-(J7-Pad1)") (class "Default")
      (node (ref "J7") (pin "1") (pinfunction "1_1") (pintype "unspecified"))
      (node (ref "J7") (pin "3") (pinfunction "3_3") (pintype "unspecified"))
      (node (ref "J7") (pin "5") (pinfunction "5_5") (pintype "unspecified"))
      (node (ref "J7") (pin "7") (pinfunction "7_7") (pintype "unspecified"))
      (node (ref "K13") (pin "4") (pinfunction "4_4") (pintype "unspecified"))
      (node (ref "K13") (pin "5") (pinfunction "5_5") (pintype "unspecified"))
      (node (ref "K14") (pin "4") (pinfunction "4_4") (pintype "unspecified"))
      (node (ref "K14") (pin "5") (pinfunction "5_5") (pintype "unspecified"))
      (node (ref "K15") (pin "4") (pinfunction "4_4") (pintype "unspecified"))
      (node (ref "K15") (pin "5") (pinfunction "5_5") (pintype "unspecified"))
      (node (ref "K16") (pin "4") (pinfunction "4_4") (pintype "unspecified"))
      (node (ref "K16") (pin "5") (pinfunction "5_5") (pintype "unspecified"))
    )
    (net (code "32") (name "Net-(J8-Pad1)") (class "Default")
      (node (ref "J8") (pin "1") (pinfunction "1_1") (pintype "unspecified"))
      (node (ref "J8") (pin "3") (pinfunction "3_3") (pintype "unspecified"))
      (node (ref "J8") (pin "5") (pinfunction "5_5") (pintype "unspecified"))
      (node (ref "J8") (pin "7") (pinfunction "7_7") (pintype "unspecified"))
      (node (ref "K13") (pin "2") (pinfunction "2_2") (pintype "unspecified"))
      (node (ref "K13") (pin "7") (pinfunction "7_7") (pintype "unspecified"))
      (node (ref "K14") (pin "2") (pinfunction "2_2") (pintype "unspecified"))
      (node (ref "K14") (pin "7") (pinfunction "7_7") (pintype "unspecified"))
      (node (ref "K15") (pin "2") (pinfunction "2_2") (pintype "unspecified"))
      (node (ref "K15") (pin "7") (pinfunction "7_7") (pintype "unspecified"))
      (node (ref "K16") (pin "2") (pinfunction "2_2") (pintype "unspecified"))
      (node (ref "K16") (pin "7") (pinfunction "7_7") (pintype "unspecified"))
    )
    (net (code "33") (name "Net-(U1-1B)") (class "Default")
      (node (ref "U1") (pin "1") (pinfunction "1B_1") (pintype "unspecified"))
      (node (ref "U5") (pin "11") (pinfunction "IO0_7_11") (pintype "unspecified"))
    )
    (net (code "34") (name "Net-(U1-2B)") (class "Default")
      (node (ref "U1") (pin "2") (pinfunction "2B_2") (pintype "unspecified"))
      (node (ref "U5") (pin "10") (pinfunction "IO0_6_10") (pintype "unspecified"))
    )
    (net (code "35") (name "Net-(U1-3B)") (class "Default")
      (node (ref "U1") (pin "3") (pinfunction "3B_3") (pintype "unspecified"))
      (node (ref "U5") (pin "9") (pinfunction "IO0_5_9") (pintype "unspecified"))
    )
    (net (code "36") (name "Net-(U1-4B)") (class "Default")
      (node (ref "U1") (pin "4") (pinfunction "4B_4") (pintype "unspecified"))
      (node (ref "U5") (pin "8") (pinfunction "IO0_4_8") (pintype "unspecified"))
    )
    (net (code "37") (name "Net-(U1-5B)") (class "Default")
      (node (ref "U1") (pin "5") (pinfunction "5B_5") (pintype "unspecified"))
      (node (ref "U5") (pin "7") (pinfunction "IO0_3_7") (pintype "unspecified"))
    )
    (net (code "38") (name "Net-(U1-6B)") (class "Default")
      (node (ref "U1") (pin "6") (pinfunction "6B_6") (pintype "unspecified"))
      (node (ref "U5") (pin "6") (pinfunction "IO0_2_6") (pintype "unspecified"))
    )
    (net (code "39") (name "Net-(U1-7B)") (class "Default")
      (node (ref "U1") (pin "7") (pinfunction "7B_7") (pintype "unspecified"))
      (node (ref "U5") (pin "5") (pinfunction "IO0_1_5") (pintype "unspecified"))
    )
    (net (code "40") (name "Net-(U1-8B)") (class "Default")
      (node (ref "U1") (pin "8") (pinfunction "8B_8") (pintype "unspecified"))
      (node (ref "U5") (pin "4") (pinfunction "IO0_0_4") (pintype "unspecified"))
    )
    (net (code "41") (name "Net-(U2-1B)") (class "Default")
      (node (ref "U2") (pin "1") (pinfunction "1B_1") (pintype "unspecified"))
      (node (ref "U5") (pin "20") (pinfunction "IO1_7_20") (pintype "unspecified"))
    )
    (net (code "42") (name "Net-(U2-2B)") (class "Default")
      (node (ref "U2") (pin "2") (pinfunction "2B_2") (pintype "unspecified"))
      (node (ref "U5") (pin "19") (pinfunction "IO1_6_19") (pintype "unspecified"))
    )
    (net (code "43") (name "Net-(U2-3B)") (class "Default")
      (node (ref "U2") (pin "3") (pinfunction "3B_3") (pintype "unspecified"))
      (node (ref "U5") (pin "18") (pinfunction "IO1_5_18") (pintype "unspecified"))
    )
    (net (code "44") (name "Net-(U2-4B)") (class "Default")
      (node (ref "U2") (pin "4") (pinfunction "4B_4") (pintype "unspecified"))
      (node (ref "U5") (pin "17") (pinfunction "IO1_4_17") (pintype "unspecified"))
    )
    (net (code "45") (name "Net-(U2-5B)") (class "Default")
      (node (ref "U2") (pin "5") (pinfunction "5B_5") (pintype "unspecified"))
      (node (ref "U5") (pin "16") (pinfunction "IO1_3_16") (pintype "unspecified"))
    )
    (net (code "46") (name "Net-(U2-6B)") (class "Default")
      (node (ref "U2") (pin "6") (pinfunction "6B_6") (pintype "unspecified"))
      (node (ref "U5") (pin "15") (pinfunction "IO1_2_15") (pintype "unspecified"))
    )
    (net (code "47") (name "Net-(U2-7B)") (class "Default")
      (node (ref "U2") (pin "7") (pinfunction "7B_7") (pintype "unspecified"))
      (node (ref "U5") (pin "14") (pinfunction "IO1_1_14") (pintype "unspecified"))
    )
    (net (code "48") (name "Net-(U2-8B)") (class "Default")
      (node (ref "U2") (pin "8") (pinfunction "8B_8") (pintype "unspecified"))
      (node (ref "U5") (pin "13") (pinfunction "IO1_0_13") (pintype "unspecified"))
    )
    (net (code "49") (name "Net-(U3-IN2D)") (class "Default")
      (node (ref "U3") (pin "13") (pinfunction "IN2D_13") (pintype "unspecified"))
      (node (ref "U3") (pin "3") (pinfunction "OUTA_3") (pintype "unspecified"))
    )
    (net (code "50") (name "Net-(U4-A0)") (class "Default")
      (node (ref "R17") (pin "2") (pinfunction "2_2") (pintype "unspecified"))
      (node (ref "U4") (pin "1") (pinfunction "A0_1") (pintype "unspecified"))
    )
    (net (code "51") (name "Net-(U4-A1)") (class "Default")
      (node (ref "R18") (pin "2") (pinfunction "2_2") (pintype "unspecified"))
      (node (ref "U4") (pin "2") (pinfunction "A1_2") (pintype "unspecified"))
    )
    (net (code "52") (name "Net-(U4-A2)") (class "Default")
      (node (ref "R19") (pin "2") (pinfunction "2_2") (pintype "unspecified"))
      (node (ref "U4") (pin "3") (pinfunction "A2_3") (pintype "unspecified"))
    )
    (net (code "53") (name "Net-(U4-LED0)") (class "Default")
      (node (ref "R16") (pin "1") (pinfunction "1_1") (pintype "unspecified"))
      (node (ref "U4") (pin "6") (pinfunction "LED0_6") (pintype "unspecified"))
    )
    (net (code "54") (name "Net-(U4-LED1)") (class "Default")
      (node (ref "R14") (pin "1") (pinfunction "1_1") (pintype "unspecified"))
      (node (ref "U4") (pin "7") (pinfunction "LED1_7") (pintype "unspecified"))
    )
    (net (code "55") (name "Net-(U4-LED2)") (class "Default")
      (node (ref "R12") (pin "1") (pinfunction "1_1") (pintype "unspecified"))
      (node (ref "U4") (pin "8") (pinfunction "LED2_8") (pintype "unspecified"))
    )
    (net (code "56") (name "Net-(U4-LED3)") (class "Default")
      (node (ref "R10") (pin "1") (pinfunction "1_1") (pintype "unspecified"))
      (node (ref "U4") (pin "9") (pinfunction "LED3_9") (pintype "unspecified"))
    )
    (net (code "57") (name "Net-(U4-LED4)") (class "Default")
      (node (ref "R8") (pin "1") (pinfunction "1_1") (pintype "unspecified"))
      (node (ref "U4") (pin "10") (pinfunction "LED4_10") (pintype "unspecified"))
    )
    (net (code "58") (name "Net-(U4-LED5)") (class "Default")
      (node (ref "R6") (pin "1") (pinfunction "1_1") (pintype "unspecified"))
      (node (ref "U4") (pin "11") (pinfunction "LED5_11") (pintype "unspecified"))
    )
    (net (code "59") (name "Net-(U4-LED6)") (class "Default")
      (node (ref "R4") (pin "1") (pinfunction "1_1") (pintype "unspecified"))
      (node (ref "U4") (pin "12") (pinfunction "LED6_12") (pintype "unspecified"))
    )
    (net (code "60") (name "Net-(U4-LED7)") (class "Default")
      (node (ref "R2") (pin "1") (pinfunction "1_1") (pintype "unspecified"))
      (node (ref "U4") (pin "13") (pinfunction "LED7_13") (pintype "unspecified"))
    )
    (net (code "61") (name "Net-(U4-LED8)") (class "Default")
      (node (ref "R1") (pin "1") (pinfunction "1_1") (pintype "unspecified"))
      (node (ref "U4") (pin "15") (pinfunction "LED8_15") (pintype "unspecified"))
    )
    (net (code "62") (name "Net-(U4-LED9)") (class "Default")
      (node (ref "R3") (pin "1") (pinfunction "1_1") (pintype "unspecified"))
      (node (ref "U4") (pin "16") (pinfunction "LED9_16") (pintype "unspecified"))
    )
    (net (code "63") (name "Net-(U4-LED10)") (class "Default")
      (node (ref "R5") (pin "1") (pinfunction "1_1") (pintype "unspecified"))
      (node (ref "U4") (pin "17") (pinfunction "LED10_17") (pintype "unspecified"))
    )
    (net (code "64") (name "Net-(U4-LED11)") (class "Default")
      (node (ref "R7") (pin "1") (pinfunction "1_1") (pintype "unspecified"))
      (node (ref "U4") (pin "18") (pinfunction "LED11_18") (pintype "unspecified"))
    )
    (net (code "65") (name "Net-(U4-LED12)") (class "Default")
      (node (ref "R9") (pin "1") (pinfunction "1_1") (pintype "unspecified"))
      (node (ref "U4") (pin "19") (pinfunction "LED12_19") (pintype "unspecified"))
    )
    (net (code "66") (name "Net-(U4-LED13)") (class "Default")
      (node (ref "R11") (pin "1") (pinfunction "1_1") (pintype "unspecified"))
      (node (ref "U4") (pin "20") (pinfunction "LED13_20") (pintype "unspecified"))
    )
    (net (code "67") (name "Net-(U4-LED14)") (class "Default")
      (node (ref "R13") (pin "1") (pinfunction "1_1") (pintype "unspecified"))
      (node (ref "U4") (pin "21") (pinfunction "LED14_21") (pintype "unspecified"))
    )
    (net (code "68") (name "Net-(U4-LED15)") (class "Default")
      (node (ref "R15") (pin "1") (pinfunction "1_1") (pintype "unspecified"))
      (node (ref "U4") (pin "22") (pinfunction "LED15_22") (pintype "unspecified"))
    )
    (net (code "69") (name "Net-(U6-WP#)") (class "Default")
      (node (ref "J27") (pin "1") (pinfunction "1_1") (pintype "unspecified"))
      (node (ref "U6") (pin "7") (pinfunction "WP#_7") (pintype "unspecified"))
    )
    (net (code "70") (name "RST") (class "Default")
      (node (ref "PCB1") (pin "33") (pinfunction "RST_33") (pintype "unspecified"))
      (node (ref "PCB1") (pin "73") (pinfunction "RST_73") (pintype "unspecified"))
    )
    (net (code "71") (name "SCL") (class "Default")
      (node (ref "PCB1") (pin "29") (pinfunction "SCL_29") (pintype "unspecified"))
      (node (ref "PCB1") (pin "69") (pinfunction "SCL_69") (pintype "unspecified"))
      (node (ref "U4") (pin "27") (pinfunction "SDA_27") (pintype "unspecified"))
      (node (ref "U6") (pin "6") (pinfunction "SCL_6") (pintype "unspecified"))
    )
    (net (code "72") (name "SDA") (class "Default")
      (node (ref "PCB1") (pin "39") (pinfunction "SDA_39") (pintype "unspecified"))
      (node (ref "PCB1") (pin "79") (pinfunction "SDA_79") (pintype "unspecified"))
      (node (ref "U4") (pin "26") (pinfunction "SCL_26") (pintype "unspecified"))
      (node (ref "U6") (pin "5") (pinfunction "SDA_5") (pintype "unspecified"))
    )
    (net (code "73") (name "TRACK-1-1") (class "Default")
      (node (ref "PCB1") (pin "10") (pinfunction "BI-1_10") (pintype "unspecified"))
      (node (ref "PCB1") (pin "50") (pinfunction "BO-1_50") (pintype "unspecified"))
    )
    (net (code "74") (name "TRACK-1-2") (class "Default")
      (node (ref "PCB1") (pin "11") (pinfunction "BI-2_11") (pintype "unspecified"))
      (node (ref "PCB1") (pin "51") (pinfunction "BO-2_51") (pintype "unspecified"))
    )
    (net (code "75") (name "TRACK-2-1") (class "Default")
      (node (ref "PCB1") (pin "12") (pinfunction "BI-3_12") (pintype "unspecified"))
      (node (ref "PCB1") (pin "52") (pinfunction "BO-3_52") (pintype "unspecified"))
    )
    (net (code "76") (name "TRACK-2-2") (class "Default")
      (node (ref "PCB1") (pin "13") (pinfunction "BI-4_13") (pintype "unspecified"))
      (node (ref "PCB1") (pin "53") (pinfunction "BO-4_53") (pintype "unspecified"))
    )
    (net (code "77") (name "TRACK-3-1") (class "Default")
      (node (ref "PCB1") (pin "14") (pinfunction "BI-5_14") (pintype "unspecified"))
      (node (ref "PCB1") (pin "54") (pinfunction "BO-5_54") (pintype "unspecified"))
    )
    (net (code "78") (name "TRACK-3-2") (class "Default")
      (node (ref "PCB1") (pin "15") (pinfunction "BI-6_15") (pintype "unspecified"))
      (node (ref "PCB1") (pin "55") (pinfunction "BO-6_55") (pintype "unspecified"))
    )
    (net (code "79") (name "TRACK-4-1") (class "Default")
      (node (ref "PCB1") (pin "16") (pinfunction "BI-7_16") (pintype "unspecified"))
      (node (ref "PCB1") (pin "56") (pinfunction "BO-7_56") (pintype "unspecified"))
    )
    (net (code "80") (name "TRACK-4-2") (class "Default")
      (node (ref "PCB1") (pin "17") (pinfunction "BI-8_17") (pintype "unspecified"))
      (node (ref "PCB1") (pin "57") (pinfunction "BO-8_57") (pintype "unspecified"))
    )
    (net (code "81") (name "VCC") (class "Default")
      (node (ref "C1") (pin "1") (pinfunction "1_1") (pintype "unspecified"))
      (node (ref "C2") (pin "2") (pinfunction "2_2") (pintype "unspecified"))
      (node (ref "C4") (pin "2") (pinfunction "2_2") (pintype "unspecified"))
      (node (ref "C5") (pin "1") (pinfunction "1_1") (pintype "unspecified"))
      (node (ref "J10") (pin "1") (pinfunction "1_1") (pintype "input"))
      (node (ref "J13") (pin "1") (pinfunction "1_1") (pintype "input"))
      (node (ref "J14") (pin "1") (pinfunction "1_1") (pintype "input"))
      (node (ref "J15") (pin "1") (pinfunction "1_1") (pintype "input"))
      (node (ref "J16") (pin "1") (pinfunction "1_1") (pintype "input"))
      (node (ref "J17") (pin "1") (pinfunction "1_1") (pintype "input"))
      (node (ref "J18") (pin "1") (pinfunction "1_1") (pintype "input"))
      (node (ref "J19") (pin "1") (pinfunction "1_1") (pintype "input"))
      (node (ref "J20") (pin "1") (pinfunction "1_1") (pintype "input"))
      (node (ref "J21") (pin "1") (pinfunction "1_1") (pintype "input"))
      (node (ref "J22") (pin "1") (pinfunction "1_1") (pintype "input"))
      (node (ref "J23") (pin "1") (pinfunction "1_1") (pintype "input"))
      (node (ref "J24") (pin "1") (pinfunction "1_1") (pintype "input"))
      (node (ref "J25") (pin "1") (pinfunction "1_1") (pintype "input"))
      (node (ref "J26") (pin "1") (pinfunction "1_1") (pintype "input"))
      (node (ref "J27") (pin "2") (pinfunction "2_2") (pintype "unspecified"))
      (node (ref "J9") (pin "1") (pinfunction "1_1") (pintype "input"))
      (node (ref "PCB1") (pin "28") (pinfunction "VCC_28") (pintype "unspecified"))
      (node (ref "PCB1") (pin "38") (pinfunction "VCC_38") (pintype "unspecified"))
      (node (ref "PCB1") (pin "68") (pinfunction "VCC_68") (pintype "unspecified"))
      (node (ref "PCB1") (pin "78") (pinfunction "VCC_78") (pintype "unspecified"))
      (node (ref "R17") (pin "1") (pinfunction "1_1") (pintype "unspecified"))
      (node (ref "R18") (pin "1") (pinfunction "1_1") (pintype "unspecified"))
      (node (ref "R19") (pin "1") (pinfunction "1_1") (pintype "unspecified"))
      (node (ref "R22") (pin "1") (pinfunction "1_1") (pintype "unspecified"))
      (node (ref "R23") (pin "1") (pinfunction "1_1") (pintype "unspecified"))
      (node (ref "U3") (pin "14") (pinfunction "VDD_14") (pintype "unspecified"))
      (node (ref "U4") (pin "28") (pinfunction "VDD_28") (pintype "unspecified"))
      (node (ref "U6") (pin "8") (pinfunction "VCC_8") (pintype "unspecified"))
    )
    (net (code "82") (name "VS") (class "Default")
      (node (ref "PCB1") (pin "41") (pinfunction "PI-2_41") (pintype "unspecified"))
      (node (ref "PCB1") (pin "81") (pinfunction "PO-2_81") (pintype "unspecified"))
    )
    (net (code "83") (name "unconnected-(J1-Pad2)") (class "Default")
      (node (ref "J1") (pin "2") (pinfunction "2_2") (pintype "unspecified"))
    )
    (net (code "84") (name "unconnected-(J1-Pad4)") (class "Default")
      (node (ref "J1") (pin "4") (pinfunction "4_4") (pintype "unspecified"))
    )
    (net (code "85") (name "unconnected-(J1-Pad6)") (class "Default")
      (node (ref "J1") (pin "6") (pinfunction "6_6") (pintype "unspecified"))
    )
    (net (code "86") (name "unconnected-(J1-Pad8)") (class "Default")
      (node (ref "J1") (pin "8") (pinfunction "8_8") (pintype "unspecified"))
    )
    (net (code "87") (name "unconnected-(J2-Pad2)") (class "Default")
      (node (ref "J2") (pin "2") (pinfunction "2_2") (pintype "unspecified"))
    )
    (net (code "88") (name "unconnected-(J2-Pad4)") (class "Default")
      (node (ref "J2") (pin "4") (pinfunction "4_4") (pintype "unspecified"))
    )
    (net (code "89") (name "unconnected-(J2-Pad6)") (class "Default")
      (node (ref "J2") (pin "6") (pinfunction "6_6") (pintype "unspecified"))
    )
    (net (code "90") (name "unconnected-(J2-Pad8)") (class "Default")
      (node (ref "J2") (pin "8") (pinfunction "8_8") (pintype "unspecified"))
    )
    (net (code "91") (name "unconnected-(J3-Pad2)") (class "Default")
      (node (ref "J3") (pin "2") (pinfunction "2_2") (pintype "unspecified"))
    )
    (net (code "92") (name "unconnected-(J3-Pad4)") (class "Default")
      (node (ref "J3") (pin "4") (pinfunction "4_4") (pintype "unspecified"))
    )
    (net (code "93") (name "unconnected-(J3-Pad6)") (class "Default")
      (node (ref "J3") (pin "6") (pinfunction "6_6") (pintype "unspecified"))
    )
    (net (code "94") (name "unconnected-(J3-Pad8)") (class "Default")
      (node (ref "J3") (pin "8") (pinfunction "8_8") (pintype "unspecified"))
    )
    (net (code "95") (name "unconnected-(J4-Pad2)") (class "Default")
      (node (ref "J4") (pin "2") (pinfunction "2_2") (pintype "unspecified"))
    )
    (net (code "96") (name "unconnected-(J4-Pad4)") (class "Default")
      (node (ref "J4") (pin "4") (pinfunction "4_4") (pintype "unspecified"))
    )
    (net (code "97") (name "unconnected-(J4-Pad6)") (class "Default")
      (node (ref "J4") (pin "6") (pinfunction "6_6") (pintype "unspecified"))
    )
    (net (code "98") (name "unconnected-(J4-Pad8)") (class "Default")
      (node (ref "J4") (pin "8") (pinfunction "8_8") (pintype "unspecified"))
    )
    (net (code "99") (name "unconnected-(J5-Pad2)") (class "Default")
      (node (ref "J5") (pin "2") (pinfunction "2_2") (pintype "unspecified"))
    )
    (net (code "100") (name "unconnected-(J5-Pad4)") (class "Default")
      (node (ref "J5") (pin "4") (pinfunction "4_4") (pintype "unspecified"))
    )
    (net (code "101") (name "unconnected-(J5-Pad6)") (class "Default")
      (node (ref "J5") (pin "6") (pinfunction "6_6") (pintype "unspecified"))
    )
    (net (code "102") (name "unconnected-(J5-Pad8)") (class "Default")
      (node (ref "J5") (pin "8") (pinfunction "8_8") (pintype "unspecified"))
    )
    (net (code "103") (name "unconnected-(J6-Pad2)") (class "Default")
      (node (ref "J6") (pin "2") (pinfunction "2_2") (pintype "unspecified"))
    )
    (net (code "104") (name "unconnected-(J6-Pad4)") (class "Default")
      (node (ref "J6") (pin "4") (pinfunction "4_4") (pintype "unspecified"))
    )
    (net (code "105") (name "unconnected-(J6-Pad6)") (class "Default")
      (node (ref "J6") (pin "6") (pinfunction "6_6") (pintype "unspecified"))
    )
    (net (code "106") (name "unconnected-(J6-Pad8)") (class "Default")
      (node (ref "J6") (pin "8") (pinfunction "8_8") (pintype "unspecified"))
    )
    (net (code "107") (name "unconnected-(J7-Pad2)") (class "Default")
      (node (ref "J7") (pin "2") (pinfunction "2_2") (pintype "unspecified"))
    )
    (net (code "108") (name "unconnected-(J7-Pad4)") (class "Default")
      (node (ref "J7") (pin "4") (pinfunction "4_4") (pintype "unspecified"))
    )
    (net (code "109") (name "unconnected-(J7-Pad6)") (class "Default")
      (node (ref "J7") (pin "6") (pinfunction "6_6") (pintype "unspecified"))
    )
    (net (code "110") (name "unconnected-(J7-Pad8)") (class "Default")
      (node (ref "J7") (pin "8") (pinfunction "8_8") (pintype "unspecified"))
    )
    (net (code "111") (name "unconnected-(J8-Pad2)") (class "Default")
      (node (ref "J8") (pin "2") (pinfunction "2_2") (pintype "unspecified"))
    )
    (net (code "112") (name "unconnected-(J8-Pad4)") (class "Default")
      (node (ref "J8") (pin "4") (pinfunction "4_4") (pintype "unspecified"))
    )
    (net (code "113") (name "unconnected-(J8-Pad6)") (class "Default")
      (node (ref "J8") (pin "6") (pinfunction "6_6") (pintype "unspecified"))
    )
    (net (code "114") (name "unconnected-(J8-Pad8)") (class "Default")
      (node (ref "J8") (pin "8") (pinfunction "8_8") (pintype "unspecified"))
    )
    (net (code "115") (name "unconnected-(J11-Pad1)") (class "Default")
      (node (ref "J11") (pin "1") (pinfunction "1_1") (pintype "unspecified"))
    )
    (net (code "116") (name "unconnected-(J11-Pad2)") (class "Default")
      (node (ref "J11") (pin "2") (pinfunction "2_2") (pintype "unspecified"))
    )
    (net (code "117") (name "unconnected-(J11-Pad3)") (class "Default")
      (node (ref "J11") (pin "3") (pinfunction "3_3") (pintype "unspecified"))
    )
    (net (code "118") (name "unconnected-(J11-Pad4)") (class "Default")
      (node (ref "J11") (pin "4") (pinfunction "4_4") (pintype "unspecified"))
    )
    (net (code "119") (name "unconnected-(J11-Pad5)") (class "Default")
      (node (ref "J11") (pin "5") (pinfunction "5_5") (pintype "unspecified"))
    )
    (net (code "120") (name "unconnected-(J11-Pad6)") (class "Default")
      (node (ref "J11") (pin "6") (pinfunction "6_6") (pintype "unspecified"))
    )
    (net (code "121") (name "unconnected-(J11-Pad7)") (class "Default")
      (node (ref "J11") (pin "7") (pinfunction "7_7") (pintype "unspecified"))
    )
    (net (code "122") (name "unconnected-(J11-Pad8)") (class "Default")
      (node (ref "J11") (pin "8") (pinfunction "8_8") (pintype "unspecified"))
    )
    (net (code "123") (name "unconnected-(J12-Pad1)") (class "Default")
      (node (ref "J12") (pin "1") (pinfunction "1_1") (pintype "unspecified"))
    )
    (net (code "124") (name "unconnected-(J12-Pad2)") (class "Default")
      (node (ref "J12") (pin "2") (pinfunction "2_2") (pintype "unspecified"))
    )
    (net (code "125") (name "unconnected-(J12-Pad3)") (class "Default")
      (node (ref "J12") (pin "3") (pinfunction "3_3") (pintype "unspecified"))
    )
    (net (code "126") (name "unconnected-(J12-Pad4)") (class "Default")
      (node (ref "J12") (pin "4") (pinfunction "4_4") (pintype "unspecified"))
    )
    (net (code "127") (name "unconnected-(J12-Pad5)") (class "Default")
      (node (ref "J12") (pin "5") (pinfunction "5_5") (pintype "unspecified"))
    )
    (net (code "128") (name "unconnected-(J12-Pad6)") (class "Default")
      (node (ref "J12") (pin "6") (pinfunction "6_6") (pintype "unspecified"))
    )
    (net (code "129") (name "unconnected-(J12-Pad7)") (class "Default")
      (node (ref "J12") (pin "7") (pinfunction "7_7") (pintype "unspecified"))
    )
    (net (code "130") (name "unconnected-(J12-Pad8)") (class "Default")
      (node (ref "J12") (pin "8") (pinfunction "8_8") (pintype "unspecified"))
    )
    (net (code "131") (name "unconnected-(K1-Pad1)") (class "Default")
      (node (ref "K1") (pin "1") (pinfunction "1_1") (pintype "unspecified"))
    )
    (net (code "132") (name "unconnected-(K1-Pad3)") (class "Default")
      (node (ref "K1") (pin "3") (pinfunction "3_3") (pintype "unspecified"))
    )
    (net (code "133") (name "unconnected-(K1-Pad6)") (class "Default")
      (node (ref "K1") (pin "6") (pinfunction "6_6") (pintype "unspecified"))
    )
    (net (code "134") (name "unconnected-(K1-Pad8)") (class "Default")
      (node (ref "K1") (pin "8") (pinfunction "8_8") (pintype "unspecified"))
    )
    (net (code "135") (name "unconnected-(K2-Pad1)") (class "Default")
      (node (ref "K2") (pin "1") (pinfunction "1_1") (pintype "unspecified"))
    )
    (net (code "136") (name "unconnected-(K2-Pad3)") (class "Default")
      (node (ref "K2") (pin "3") (pinfunction "3_3") (pintype "unspecified"))
    )
    (net (code "137") (name "unconnected-(K2-Pad6)") (class "Default")
      (node (ref "K2") (pin "6") (pinfunction "6_6") (pintype "unspecified"))
    )
    (net (code "138") (name "unconnected-(K2-Pad8)") (class "Default")
      (node (ref "K2") (pin "8") (pinfunction "8_8") (pintype "unspecified"))
    )
    (net (code "139") (name "unconnected-(K3-Pad1)") (class "Default")
      (node (ref "K3") (pin "1") (pinfunction "1_1") (pintype "unspecified"))
    )
    (net (code "140") (name "unconnected-(K3-Pad3)") (class "Default")
      (node (ref "K3") (pin "3") (pinfunction "3_3") (pintype "unspecified"))
    )
    (net (code "141") (name "unconnected-(K3-Pad6)") (class "Default")
      (node (ref "K3") (pin "6") (pinfunction "6_6") (pintype "unspecified"))
    )
    (net (code "142") (name "unconnected-(K3-Pad8)") (class "Default")
      (node (ref "K3") (pin "8") (pinfunction "8_8") (pintype "unspecified"))
    )
    (net (code "143") (name "unconnected-(K4-Pad1)") (class "Default")
      (node (ref "K4") (pin "1") (pinfunction "1_1") (pintype "unspecified"))
    )
    (net (code "144") (name "unconnected-(K4-Pad3)") (class "Default")
      (node (ref "K4") (pin "3") (pinfunction "3_3") (pintype "unspecified"))
    )
    (net (code "145") (name "unconnected-(K4-Pad6)") (class "Default")
      (node (ref "K4") (pin "6") (pinfunction "6_6") (pintype "unspecified"))
    )
    (net (code "146") (name "unconnected-(K4-Pad8)") (class "Default")
      (node (ref "K4") (pin "8") (pinfunction "8_8") (pintype "unspecified"))
    )
    (net (code "147") (name "unconnected-(K5-Pad1)") (class "Default")
      (node (ref "K5") (pin "1") (pinfunction "1_1") (pintype "unspecified"))
    )
    (net (code "148") (name "unconnected-(K5-Pad3)") (class "Default")
      (node (ref "K5") (pin "3") (pinfunction "3_3") (pintype "unspecified"))
    )
    (net (code "149") (name "unconnected-(K5-Pad6)") (class "Default")
      (node (ref "K5") (pin "6") (pinfunction "6_6") (pintype "unspecified"))
    )
    (net (code "150") (name "unconnected-(K5-Pad8)") (class "Default")
      (node (ref "K5") (pin "8") (pinfunction "8_8") (pintype "unspecified"))
    )
    (net (code "151") (name "unconnected-(K6-Pad1)") (class "Default")
      (node (ref "K6") (pin "1") (pinfunction "1_1") (pintype "unspecified"))
    )
    (net (code "152") (name "unconnected-(K6-Pad3)") (class "Default")
      (node (ref "K6") (pin "3") (pinfunction "3_3") (pintype "unspecified"))
    )
    (net (code "153") (name "unconnected-(K6-Pad6)") (class "Default")
      (node (ref "K6") (pin "6") (pinfunction "6_6") (pintype "unspecified"))
    )
    (net (code "154") (name "unconnected-(K6-Pad8)") (class "Default")
      (node (ref "K6") (pin "8") (pinfunction "8_8") (pintype "unspecified"))
    )
    (net (code "155") (name "unconnected-(K7-Pad1)") (class "Default")
      (node (ref "K7") (pin "1") (pinfunction "1_1") (pintype "unspecified"))
    )
    (net (code "156") (name "unconnected-(K7-Pad3)") (class "Default")
      (node (ref "K7") (pin "3") (pinfunction "3_3") (pintype "unspecified"))
    )
    (net (code "157") (name "unconnected-(K7-Pad6)") (class "Default")
      (node (ref "K7") (pin "6") (pinfunction "6_6") (pintype "unspecified"))
    )
    (net (code "158") (name "unconnected-(K7-Pad8)") (class "Default")
      (node (ref "K7") (pin "8") (pinfunction "8_8") (pintype "unspecified"))
    )
    (net (code "159") (name "unconnected-(K8-Pad1)") (class "Default")
      (node (ref "K8") (pin "1") (pinfunction "1_1") (pintype "unspecified"))
    )
    (net (code "160") (name "unconnected-(K8-Pad3)") (class "Default")
      (node (ref "K8") (pin "3") (pinfunction "3_3") (pintype "unspecified"))
    )
    (net (code "161") (name "unconnected-(K8-Pad6)") (class "Default")
      (node (ref "K8") (pin "6") (pinfunction "6_6") (pintype "unspecified"))
    )
    (net (code "162") (name "unconnected-(K8-Pad8)") (class "Default")
      (node (ref "K8") (pin "8") (pinfunction "8_8") (pintype "unspecified"))
    )
    (net (code "163") (name "unconnected-(K9-Pad1)") (class "Default")
      (node (ref "K9") (pin "1") (pinfunction "1_1") (pintype "unspecified"))
    )
    (net (code "164") (name "unconnected-(K9-Pad3)") (class "Default")
      (node (ref "K9") (pin "3") (pinfunction "3_3") (pintype "unspecified"))
    )
    (net (code "165") (name "unconnected-(K9-Pad6)") (class "Default")
      (node (ref "K9") (pin "6") (pinfunction "6_6") (pintype "unspecified"))
    )
    (net (code "166") (name "unconnected-(K9-Pad8)") (class "Default")
      (node (ref "K9") (pin "8") (pinfunction "8_8") (pintype "unspecified"))
    )
    (net (code "167") (name "unconnected-(K10-Pad1)") (class "Default")
      (node (ref "K10") (pin "1") (pinfunction "1_1") (pintype "unspecified"))
    )
    (net (code "168") (name "unconnected-(K10-Pad3)") (class "Default")
      (node (ref "K10") (pin "3") (pinfunction "3_3") (pintype "unspecified"))
    )
    (net (code "169") (name "unconnected-(K10-Pad6)") (class "Default")
      (node (ref "K10") (pin "6") (pinfunction "6_6") (pintype "unspecified"))
    )
    (net (code "170") (name "unconnected-(K10-Pad8)") (class "Default")
      (node (ref "K10") (pin "8") (pinfunction "8_8") (pintype "unspecified"))
    )
    (net (code "171") (name "unconnected-(K11-Pad1)") (class "Default")
      (node (ref "K11") (pin "1") (pinfunction "1_1") (pintype "unspecified"))
    )
    (net (code "172") (name "unconnected-(K11-Pad3)") (class "Default")
      (node (ref "K11") (pin "3") (pinfunction "3_3") (pintype "unspecified"))
    )
    (net (code "173") (name "unconnected-(K11-Pad6)") (class "Default")
      (node (ref "K11") (pin "6") (pinfunction "6_6") (pintype "unspecified"))
    )
    (net (code "174") (name "unconnected-(K11-Pad8)") (class "Default")
      (node (ref "K11") (pin "8") (pinfunction "8_8") (pintype "unspecified"))
    )
    (net (code "175") (name "unconnected-(K12-Pad1)") (class "Default")
      (node (ref "K12") (pin "1") (pinfunction "1_1") (pintype "unspecified"))
    )
    (net (code "176") (name "unconnected-(K12-Pad3)") (class "Default")
      (node (ref "K12") (pin "3") (pinfunction "3_3") (pintype "unspecified"))
    )
    (net (code "177") (name "unconnected-(K12-Pad6)") (class "Default")
      (node (ref "K12") (pin "6") (pinfunction "6_6") (pintype "unspecified"))
    )
    (net (code "178") (name "unconnected-(K12-Pad8)") (class "Default")
      (node (ref "K12") (pin "8") (pinfunction "8_8") (pintype "unspecified"))
    )
    (net (code "179") (name "unconnected-(K13-Pad1)") (class "Default")
      (node (ref "K13") (pin "1") (pinfunction "1_1") (pintype "unspecified"))
    )
    (net (code "180") (name "unconnected-(K13-Pad3)") (class "Default")
      (node (ref "K13") (pin "3") (pinfunction "3_3") (pintype "unspecified"))
    )
    (net (code "181") (name "unconnected-(K13-Pad6)") (class "Default")
      (node (ref "K13") (pin "6") (pinfunction "6_6") (pintype "unspecified"))
    )
    (net (code "182") (name "unconnected-(K13-Pad8)") (class "Default")
      (node (ref "K13") (pin "8") (pinfunction "8_8") (pintype "unspecified"))
    )
    (net (code "183") (name "unconnected-(K14-Pad1)") (class "Default")
      (node (ref "K14") (pin "1") (pinfunction "1_1") (pintype "unspecified"))
    )
    (net (code "184") (name "unconnected-(K14-Pad3)") (class "Default")
      (node (ref "K14") (pin "3") (pinfunction "3_3") (pintype "unspecified"))
    )
    (net (code "185") (name "unconnected-(K14-Pad6)") (class "Default")
      (node (ref "K14") (pin "6") (pinfunction "6_6") (pintype "unspecified"))
    )
    (net (code "186") (name "unconnected-(K14-Pad8)") (class "Default")
      (node (ref "K14") (pin "8") (pinfunction "8_8") (pintype "unspecified"))
    )
    (net (code "187") (name "unconnected-(K15-Pad1)") (class "Default")
      (node (ref "K15") (pin "1") (pinfunction "1_1") (pintype "unspecified"))
    )
    (net (code "188") (name "unconnected-(K15-Pad3)") (class "Default")
      (node (ref "K15") (pin "3") (pinfunction "3_3") (pintype "unspecified"))
    )
    (net (code "189") (name "unconnected-(K15-Pad6)") (class "Default")
      (node (ref "K15") (pin "6") (pinfunction "6_6") (pintype "unspecified"))
    )
    (net (code "190") (name "unconnected-(K15-Pad8)") (class "Default")
      (node (ref "K15") (pin "8") (pinfunction "8_8") (pintype "unspecified"))
    )
    (net (code "191") (name "unconnected-(K16-Pad1)") (class "Default")
      (node (ref "K16") (pin "1") (pinfunction "1_1") (pintype "unspecified"))
    )
    (net (code "192") (name "unconnected-(K16-Pad3)") (class "Default")
      (node (ref "K16") (pin "3") (pinfunction "3_3") (pintype "unspecified"))
    )
    (net (code "193") (name "unconnected-(K16-Pad6)") (class "Default")
      (node (ref "K16") (pin "6") (pinfunction "6_6") (pintype "unspecified"))
    )
    (net (code "194") (name "unconnected-(K16-Pad8)") (class "Default")
      (node (ref "K16") (pin "8") (pinfunction "8_8") (pintype "unspecified"))
    )
    (net (code "195") (name "unconnected-(PCB1-DCC-1-Pad20)") (class "Default")
      (node (ref "PCB1") (pin "20") (pinfunction "DCC-1_20") (pintype "unspecified+no_connect"))
    )
    (net (code "196") (name "unconnected-(PCB1-DCC-1-Pad60)") (class "Default")
      (node (ref "PCB1") (pin "60") (pinfunction "DCC-1_60") (pintype "unspecified+no_connect"))
    )
    (net (code "197") (name "unconnected-(PCB1-DCC-2-Pad30)") (class "Default")
      (node (ref "PCB1") (pin "30") (pinfunction "DCC-2_30") (pintype "unspecified+no_connect"))
    )
    (net (code "198") (name "unconnected-(PCB1-DCC-2-Pad70)") (class "Default")
      (node (ref "PCB1") (pin "70") (pinfunction "DCC-2_70") (pintype "unspecified+no_connect"))
    )
    (net (code "199") (name "unconnected-(PCB1-DIO-0-Pad24)") (class "Default")
      (node (ref "PCB1") (pin "24") (pinfunction "DIO-0_24") (pintype "unspecified+no_connect"))
    )
    (net (code "200") (name "unconnected-(PCB1-DIO-0-Pad64)") (class "Default")
      (node (ref "PCB1") (pin "64") (pinfunction "DIO-0_64") (pintype "unspecified+no_connect"))
    )
    (net (code "201") (name "unconnected-(PCB1-DIO-1-Pad34)") (class "Default")
      (node (ref "PCB1") (pin "34") (pinfunction "DIO-1_34") (pintype "unspecified+no_connect"))
    )
    (net (code "202") (name "unconnected-(PCB1-DIO-1-Pad74)") (class "Default")
      (node (ref "PCB1") (pin "74") (pinfunction "DIO-1_74") (pintype "unspecified+no_connect"))
    )
    (net (code "203") (name "unconnected-(PCB1-DIO-2-Pad25)") (class "Default")
      (node (ref "PCB1") (pin "25") (pinfunction "DIO-2_25") (pintype "unspecified+no_connect"))
    )
    (net (code "204") (name "unconnected-(PCB1-DIO-2-Pad65)") (class "Default")
      (node (ref "PCB1") (pin "65") (pinfunction "DIO-2_65") (pintype "unspecified+no_connect"))
    )
    (net (code "205") (name "unconnected-(PCB1-DIO-3-Pad35)") (class "Default")
      (node (ref "PCB1") (pin "35") (pinfunction "DIO-3_35") (pintype "unspecified+no_connect"))
    )
    (net (code "206") (name "unconnected-(PCB1-DIO-3-Pad75)") (class "Default")
      (node (ref "PCB1") (pin "75") (pinfunction "DIO-3_75") (pintype "unspecified+no_connect"))
    )
    (net (code "207") (name "unconnected-(PCB1-DIO-4-Pad26)") (class "Default")
      (node (ref "PCB1") (pin "26") (pinfunction "DIO-4_26") (pintype "unspecified+no_connect"))
    )
    (net (code "208") (name "unconnected-(PCB1-DIO-4-Pad66)") (class "Default")
      (node (ref "PCB1") (pin "66") (pinfunction "DIO-4_66") (pintype "unspecified+no_connect"))
    )
    (net (code "209") (name "unconnected-(PCB1-DIO-5-Pad36)") (class "Default")
      (node (ref "PCB1") (pin "36") (pinfunction "DIO-5_36") (pintype "unspecified+no_connect"))
    )
    (net (code "210") (name "unconnected-(PCB1-DIO-5-Pad76)") (class "Default")
      (node (ref "PCB1") (pin "76") (pinfunction "DIO-5_76") (pintype "unspecified+no_connect"))
    )
    (net (code "211") (name "unconnected-(PCB1-DIO-6-Pad27)") (class "Default")
      (node (ref "PCB1") (pin "27") (pinfunction "DIO-6_27") (pintype "unspecified+no_connect"))
    )
    (net (code "212") (name "unconnected-(PCB1-DIO-6-Pad67)") (class "Default")
      (node (ref "PCB1") (pin "67") (pinfunction "DIO-6_67") (pintype "unspecified+no_connect"))
    )
    (net (code "213") (name "unconnected-(PCB1-DIO-7-Pad37)") (class "Default")
      (node (ref "PCB1") (pin "37") (pinfunction "DIO-7_37") (pintype "unspecified+no_connect"))
    )
    (net (code "214") (name "unconnected-(PCB1-DIO-7-Pad77)") (class "Default")
      (node (ref "PCB1") (pin "77") (pinfunction "DIO-7_77") (pintype "unspecified+no_connect"))
    )
    (net (code "215") (name "unconnected-(PCB1-PI-3-Pad42)") (class "Default")
      (node (ref "PCB1") (pin "42") (pinfunction "PI-3_42") (pintype "unspecified+no_connect"))
    )
    (net (code "216") (name "unconnected-(PCB1-PI-4-Pad43)") (class "Default")
      (node (ref "PCB1") (pin "43") (pinfunction "PI-4_43") (pintype "unspecified+no_connect"))
    )
    (net (code "217") (name "unconnected-(PCB1-PI-5-Pad44)") (class "Default")
      (node (ref "PCB1") (pin "44") (pinfunction "PI-5_44") (pintype "unspecified+no_connect"))
    )
    (net (code "218") (name "unconnected-(PCB1-PI-6-Pad45)") (class "Default")
      (node (ref "PCB1") (pin "45") (pinfunction "PI-6_45") (pintype "unspecified+no_connect"))
    )
    (net (code "219") (name "unconnected-(PCB1-PI-7-Pad46)") (class "Default")
      (node (ref "PCB1") (pin "46") (pinfunction "PI-7_46") (pintype "unspecified+no_connect"))
    )
    (net (code "220") (name "unconnected-(PCB1-PI-8-Pad47)") (class "Default")
      (node (ref "PCB1") (pin "47") (pinfunction "PI-8_47") (pintype "unspecified+no_connect"))
    )
    (net (code "221") (name "unconnected-(PCB1-PO-3-Pad82)") (class "Default")
      (node (ref "PCB1") (pin "82") (pinfunction "PO-3_82") (pintype "unspecified+no_connect"))
    )
    (net (code "222") (name "unconnected-(PCB1-PO-4-Pad83)") (class "Default")
      (node (ref "PCB1") (pin "83") (pinfunction "PO-4_83") (pintype "unspecified+no_connect"))
    )
    (net (code "223") (name "unconnected-(PCB1-PO-5-Pad84)") (class "Default")
      (node (ref "PCB1") (pin "84") (pinfunction "PO-5_84") (pintype "unspecified+no_connect"))
    )
    (net (code "224") (name "unconnected-(PCB1-PO-6-Pad85)") (class "Default")
      (node (ref "PCB1") (pin "85") (pinfunction "PO-6_85") (pintype "unspecified+no_connect"))
    )
    (net (code "225") (name "unconnected-(PCB1-PO-7-Pad86)") (class "Default")
      (node (ref "PCB1") (pin "86") (pinfunction "PO-7_86") (pintype "unspecified+no_connect"))
    )
    (net (code "226") (name "unconnected-(PCB1-PO-8-Pad87)") (class "Default")
      (node (ref "PCB1") (pin "87") (pinfunction "PO-8_87") (pintype "unspecified+no_connect"))
    )
    (net (code "227") (name "unconnected-(U1-1C-Pad18)") (class "Default")
      (node (ref "U1") (pin "18") (pinfunction "1C_18") (pintype "unspecified"))
    )
    (net (code "228") (name "unconnected-(U1-2C-Pad17)") (class "Default")
      (node (ref "U1") (pin "17") (pinfunction "2C_17") (pintype "unspecified"))
    )
    (net (code "229") (name "unconnected-(U1-3C-Pad16)") (class "Default")
      (node (ref "U1") (pin "16") (pinfunction "3C_16") (pintype "unspecified"))
    )
    (net (code "230") (name "unconnected-(U1-4C-Pad15)") (class "Default")
      (node (ref "U1") (pin "15") (pinfunction "4C_15") (pintype "unspecified"))
    )
    (net (code "231") (name "unconnected-(U1-5C-Pad14)") (class "Default")
      (node (ref "U1") (pin "14") (pinfunction "5C_14") (pintype "unspecified"))
    )
    (net (code "232") (name "unconnected-(U1-6C-Pad13)") (class "Default")
      (node (ref "U1") (pin "13") (pinfunction "6C_13") (pintype "unspecified"))
    )
    (net (code "233") (name "unconnected-(U1-7C-Pad12)") (class "Default")
      (node (ref "U1") (pin "12") (pinfunction "7C_12") (pintype "unspecified"))
    )
    (net (code "234") (name "unconnected-(U1-8C-Pad11)") (class "Default")
      (node (ref "U1") (pin "11") (pinfunction "8C_11") (pintype "unspecified"))
    )
    (net (code "235") (name "unconnected-(U1-COM-Pad10)") (class "Default")
      (node (ref "U1") (pin "10") (pinfunction "COM_10") (pintype "unspecified"))
    )
    (net (code "236") (name "unconnected-(U1-GND-Pad9)") (class "Default")
      (node (ref "U1") (pin "9") (pinfunction "GND_9") (pintype "unspecified"))
    )
    (net (code "237") (name "unconnected-(U2-1C-Pad18)") (class "Default")
      (node (ref "U2") (pin "18") (pinfunction "1C_18") (pintype "unspecified"))
    )
    (net (code "238") (name "unconnected-(U2-2C-Pad17)") (class "Default")
      (node (ref "U2") (pin "17") (pinfunction "2C_17") (pintype "unspecified"))
    )
    (net (code "239") (name "unconnected-(U2-3C-Pad16)") (class "Default")
      (node (ref "U2") (pin "16") (pinfunction "3C_16") (pintype "unspecified"))
    )
    (net (code "240") (name "unconnected-(U2-4C-Pad15)") (class "Default")
      (node (ref "U2") (pin "15") (pinfunction "4C_15") (pintype "unspecified"))
    )
    (net (code "241") (name "unconnected-(U2-5C-Pad14)") (class "Default")
      (node (ref "U2") (pin "14") (pinfunction "5C_14") (pintype "unspecified"))
    )
    (net (code "242") (name "unconnected-(U2-6C-Pad13)") (class "Default")
      (node (ref "U2") (pin "13") (pinfunction "6C_13") (pintype "unspecified"))
    )
    (net (code "243") (name "unconnected-(U2-7C-Pad12)") (class "Default")
      (node (ref "U2") (pin "12") (pinfunction "7C_12") (pintype "unspecified"))
    )
    (net (code "244") (name "unconnected-(U2-8C-Pad11)") (class "Default")
      (node (ref "U2") (pin "11") (pinfunction "8C_11") (pintype "unspecified"))
    )
    (net (code "245") (name "unconnected-(U2-COM-Pad10)") (class "Default")
      (node (ref "U2") (pin "10") (pinfunction "COM_10") (pintype "unspecified"))
    )
    (net (code "246") (name "unconnected-(U2-GND-Pad9)") (class "Default")
      (node (ref "U2") (pin "9") (pinfunction "GND_9") (pintype "unspecified"))
    )
    (net (code "247") (name "unconnected-(U3-OUTB-Pad4)") (class "Default")
      (node (ref "U3") (pin "4") (pinfunction "OUTB_4") (pintype "unspecified+no_connect"))
    )
    (net (code "248") (name "unconnected-(U4-EXTCLK-Pad25)") (class "Default")
      (node (ref "U4") (pin "25") (pinfunction "EXTCLK_25") (pintype "unspecified+no_connect"))
    )
    (net (code "249") (name "unconnected-(U4-OE#-Pad23)") (class "Default")
      (node (ref "U4") (pin "23") (pinfunction "OE#_23") (pintype "unspecified+no_connect"))
    )
    (net (code "250") (name "unconnected-(U5-A0-Pad21)") (class "Default")
      (node (ref "U5") (pin "21") (pinfunction "A0_21") (pintype "unspecified"))
    )
    (net (code "251") (name "unconnected-(U5-A1-Pad2)") (class "Default")
      (node (ref "U5") (pin "2") (pinfunction "A1_2") (pintype "unspecified"))
    )
    (net (code "252") (name "unconnected-(U5-A2-Pad3)") (class "Default")
      (node (ref "U5") (pin "3") (pinfunction "A2_3") (pintype "unspecified"))
    )
    (net (code "253") (name "unconnected-(U5-INT#-Pad1)") (class "Default")
      (node (ref "U5") (pin "1") (pinfunction "INT#_1") (pintype "unspecified"))
    )
    (net (code "254") (name "unconnected-(U5-SCL-Pad22)") (class "Default")
      (node (ref "U5") (pin "22") (pinfunction "SCL_22") (pintype "unspecified"))
    )
    (net (code "255") (name "unconnected-(U5-SDA-Pad23)") (class "Default")
      (node (ref "U5") (pin "23") (pinfunction "SDA_23") (pintype "unspecified"))
    )
    (net (code "256") (name "unconnected-(U5-VDD-Pad24)") (class "Default")
      (node (ref "U5") (pin "24") (pinfunction "VDD_24") (pintype "unspecified"))
    )
    (net (code "257") (name "unconnected-(U5-VSS-Pad12)") (class "Default")
      (node (ref "U5") (pin "12") (pinfunction "VSS_12") (pintype "unspecified"))
    )
  )
)
